# PWM-Power-Box_simplified_R1_0.net
KiCad netlist of a schematic drawn in EAGLE
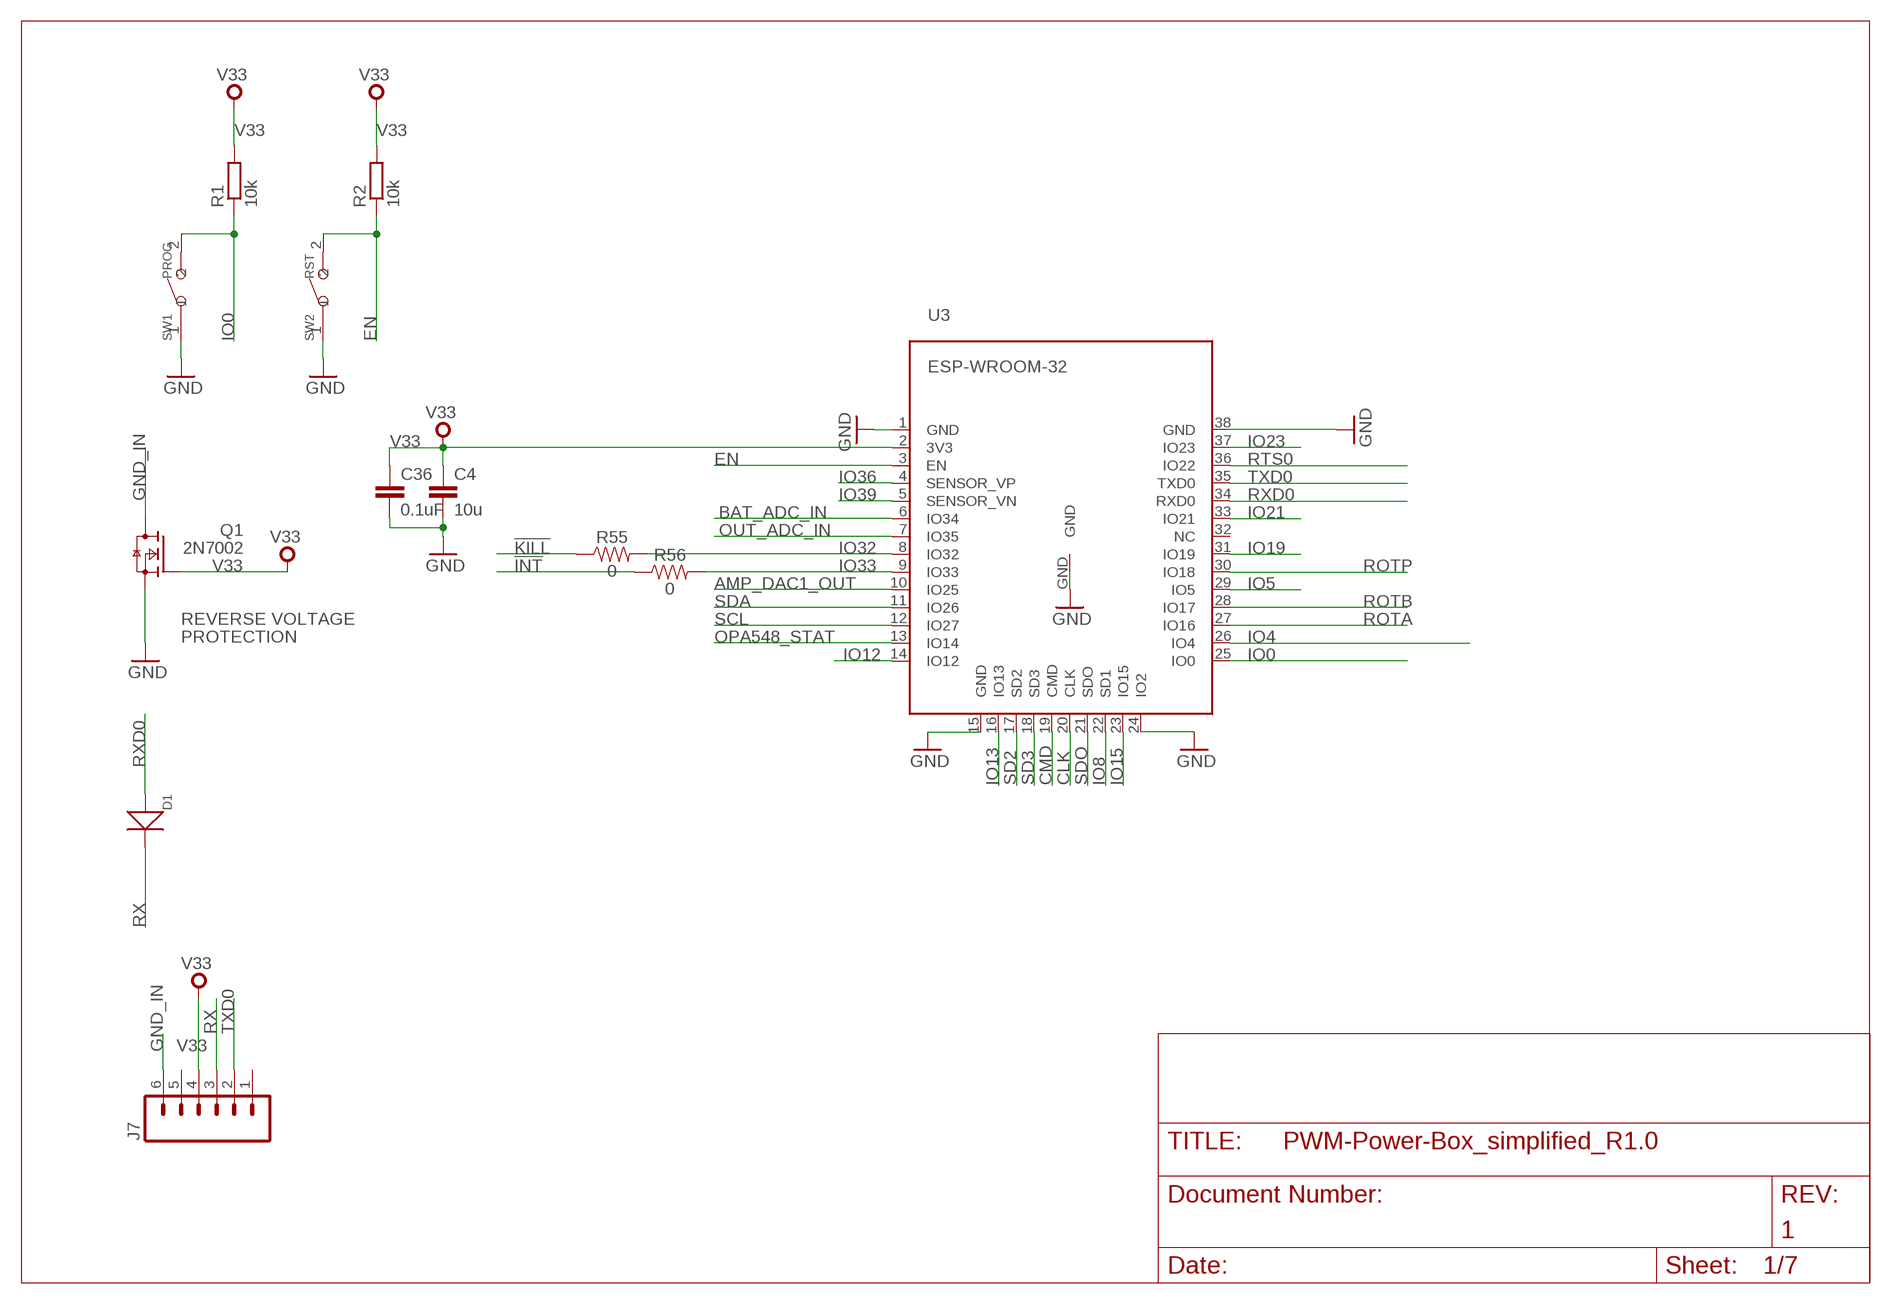
[diagram p0: schematic, sheet 1]
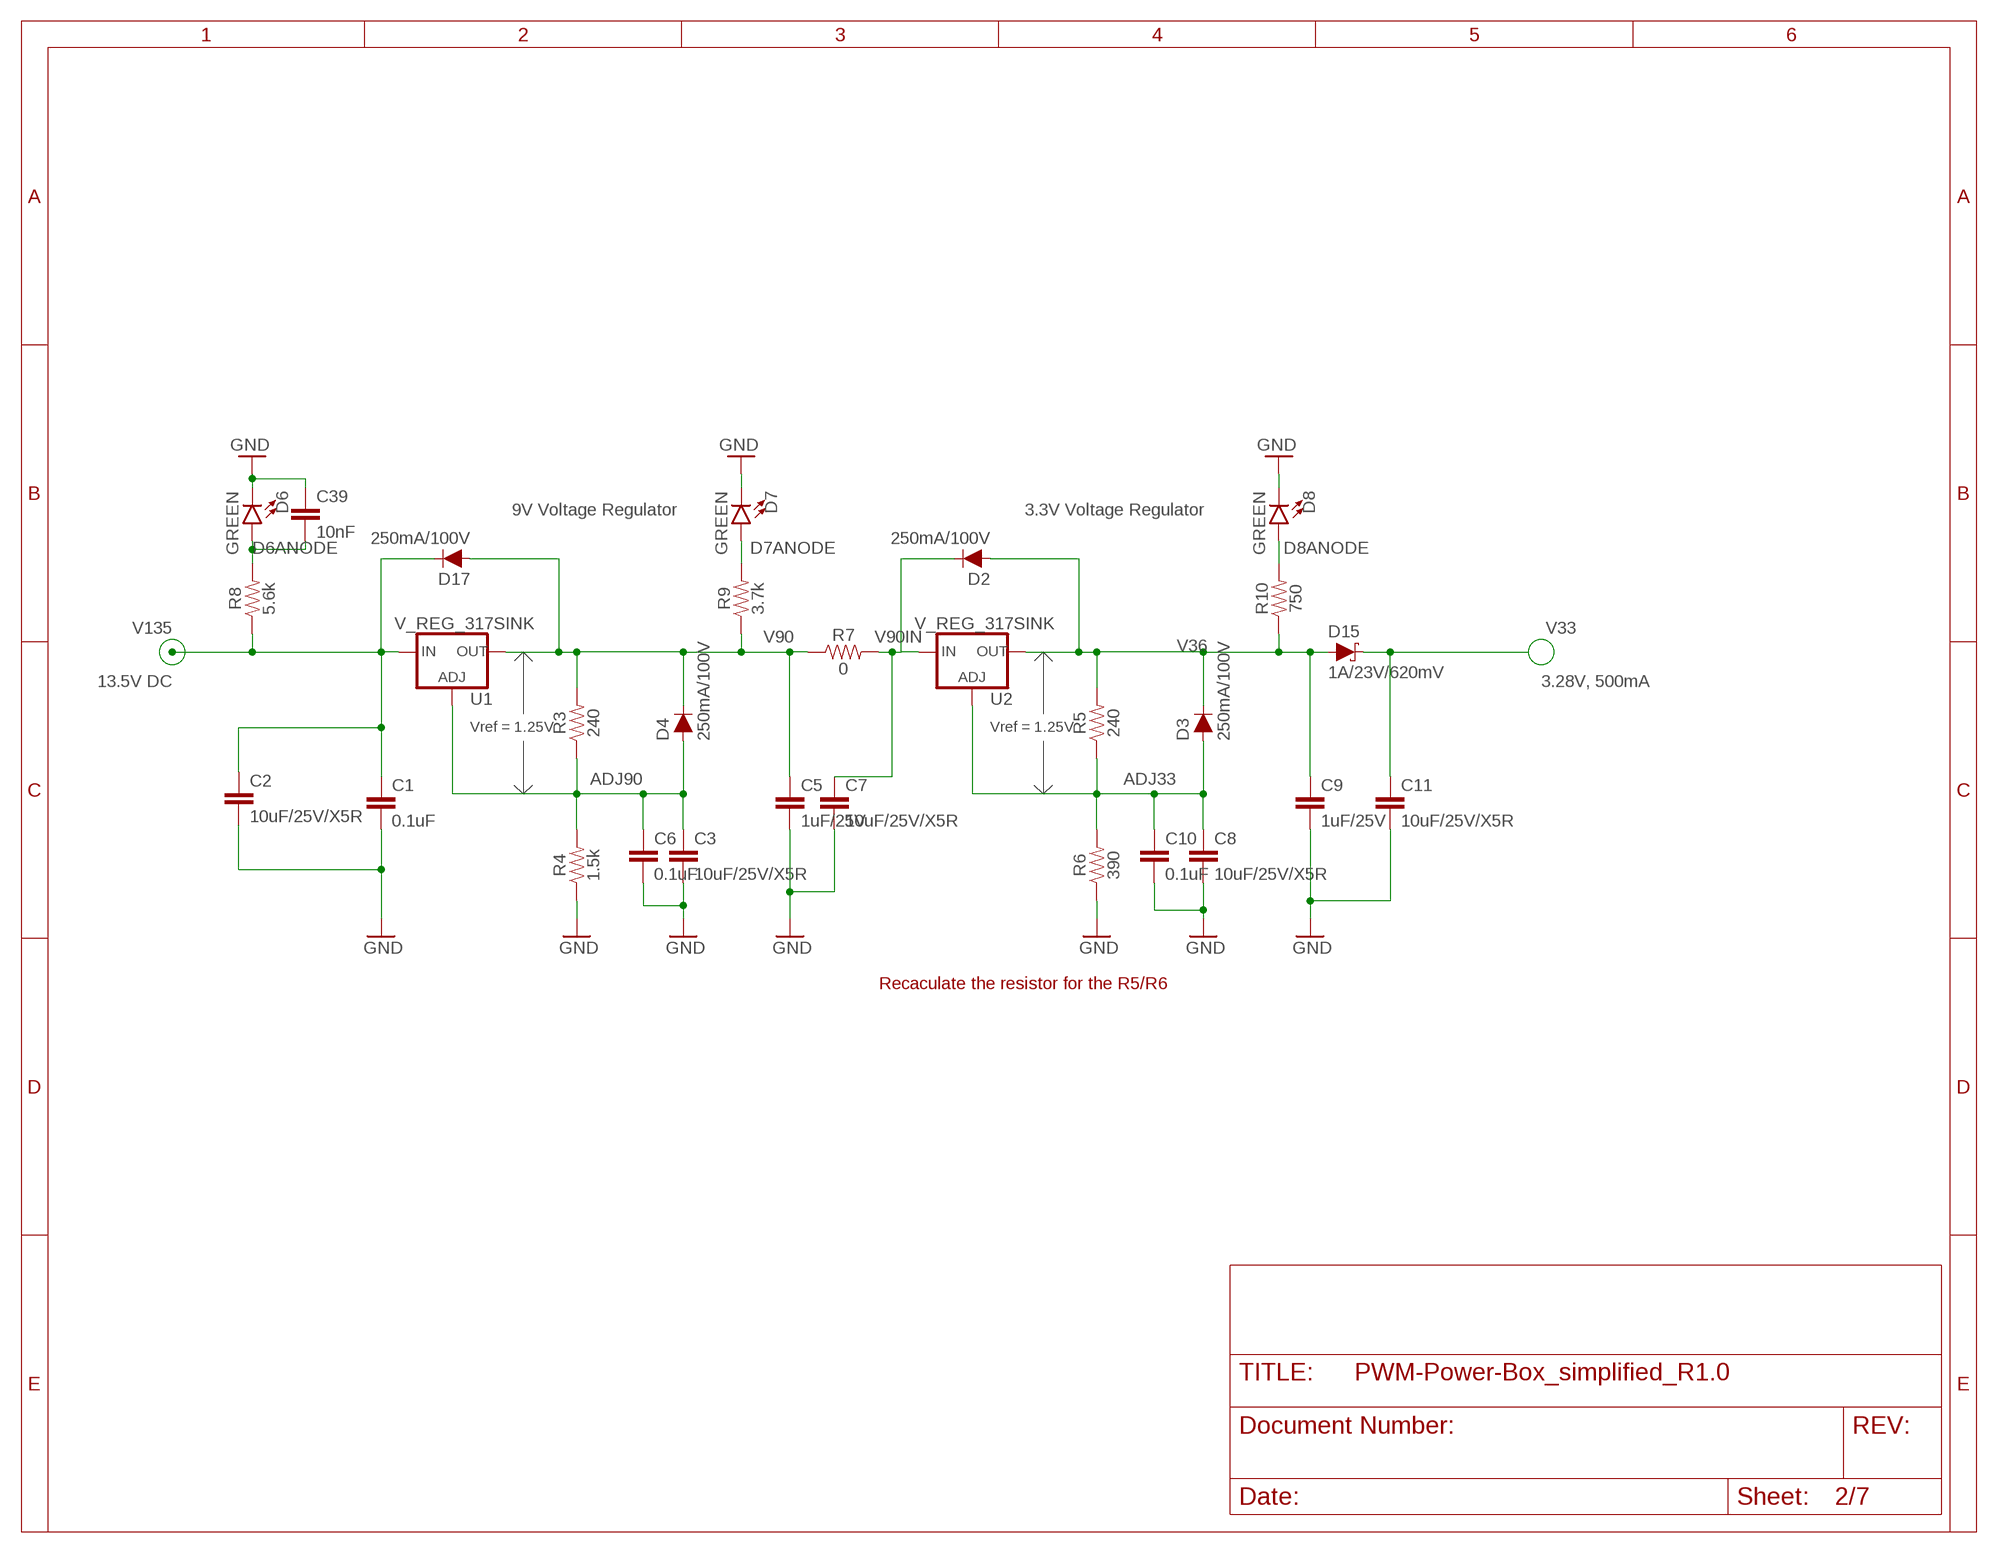
[diagram p1: schematic, sheet 2]
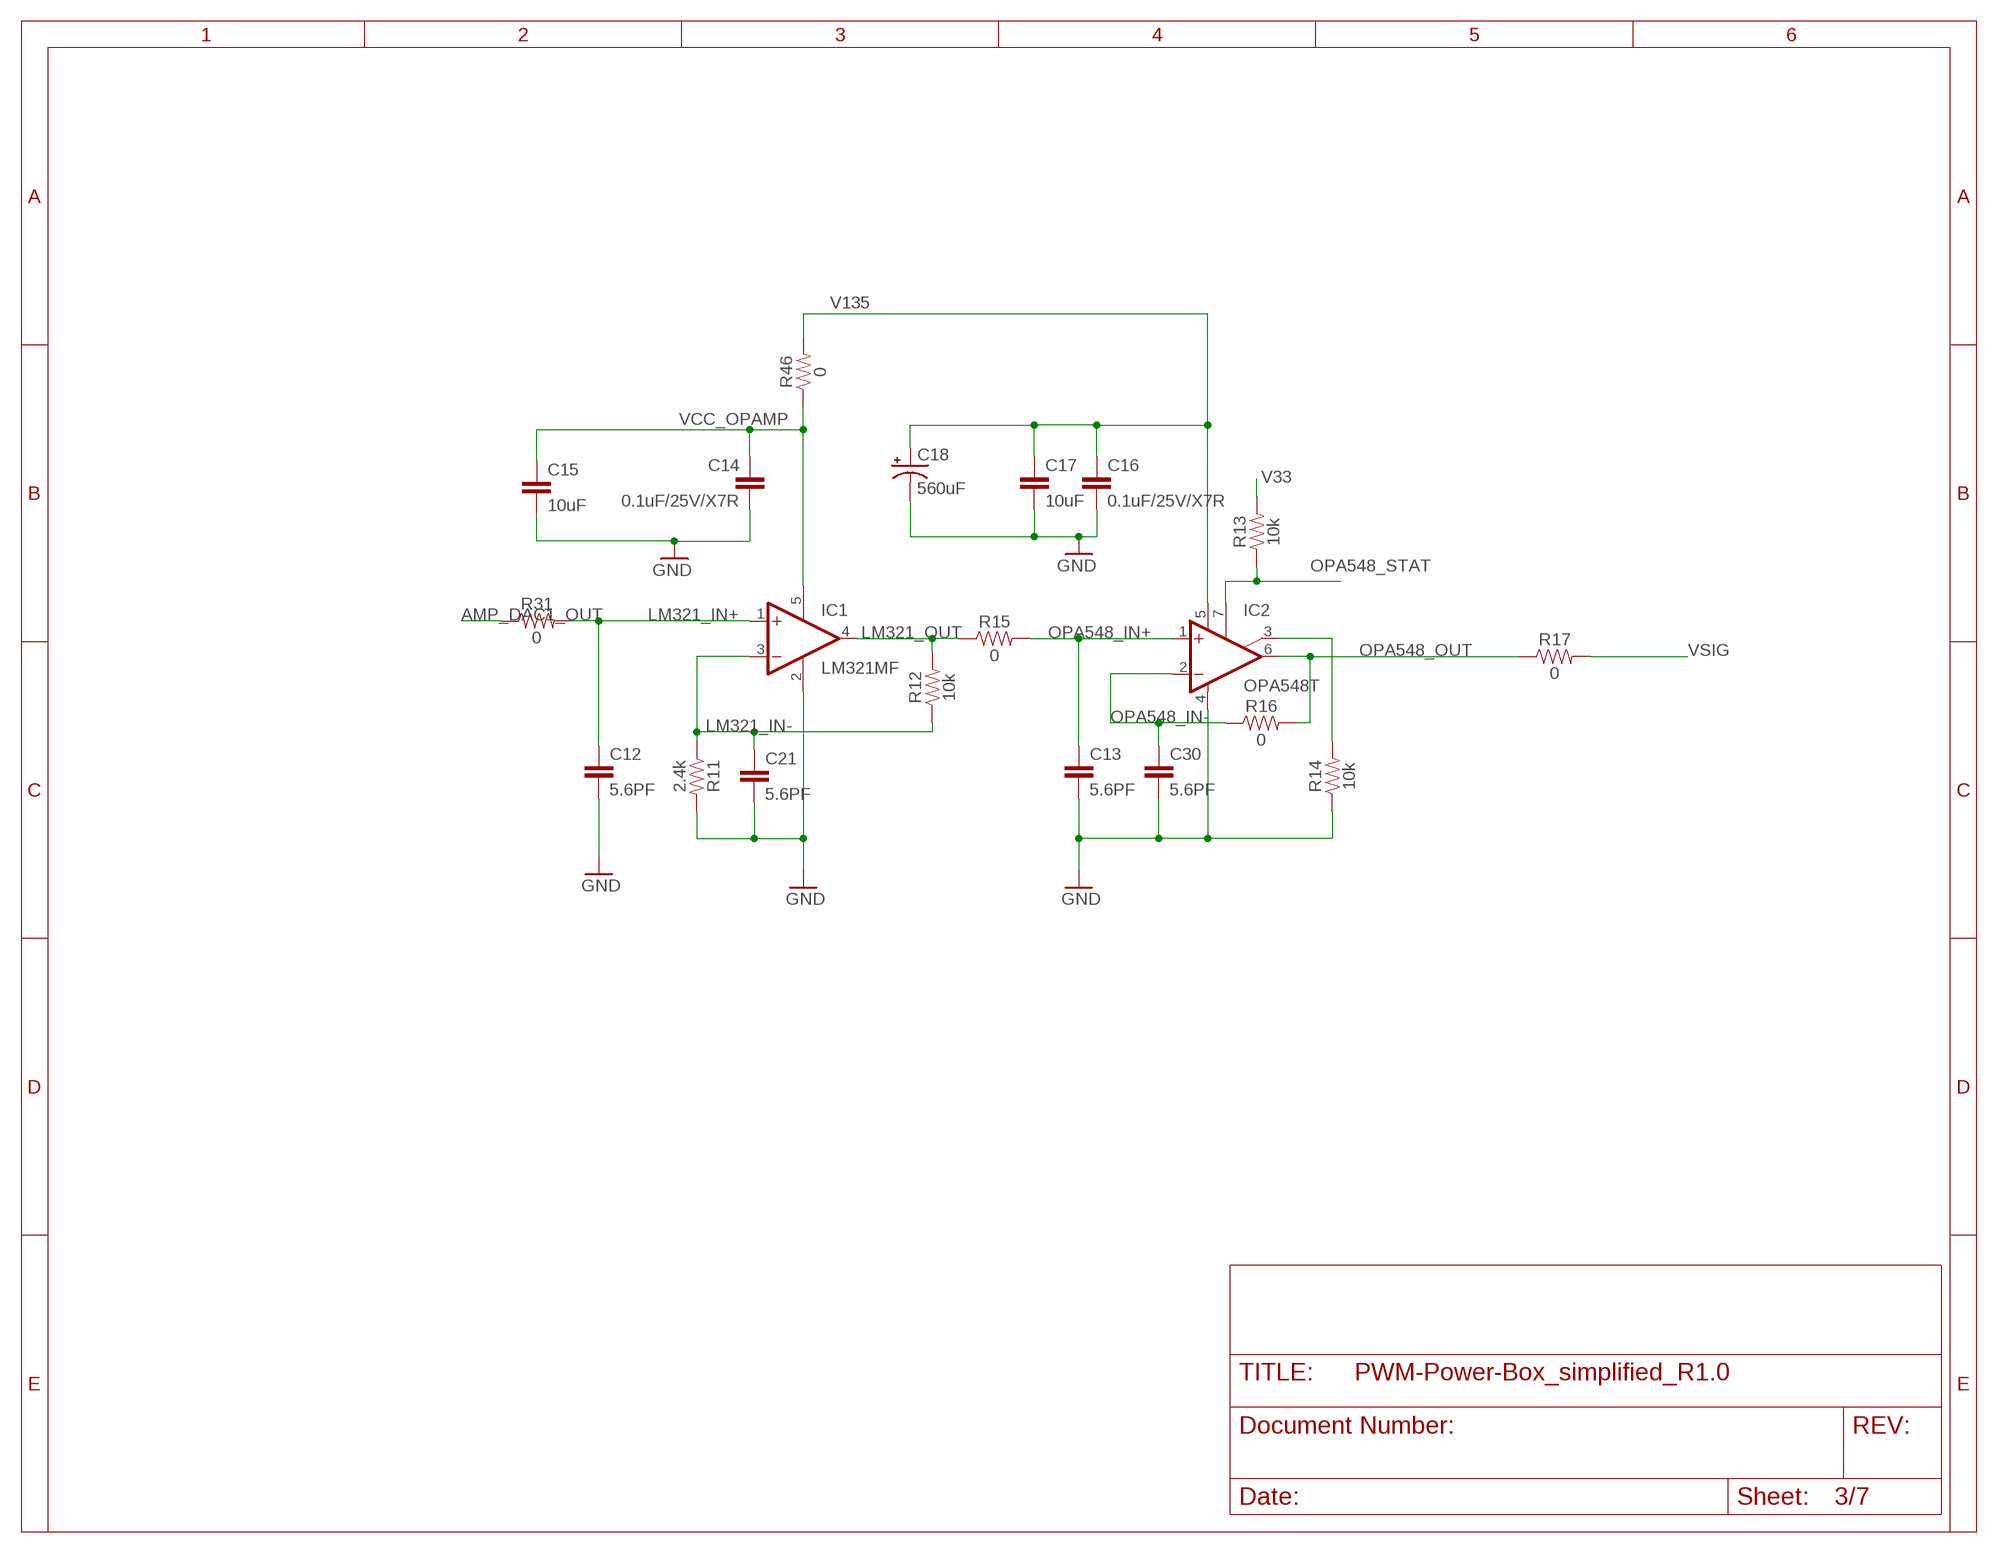
[diagram p2: schematic, sheet 3]
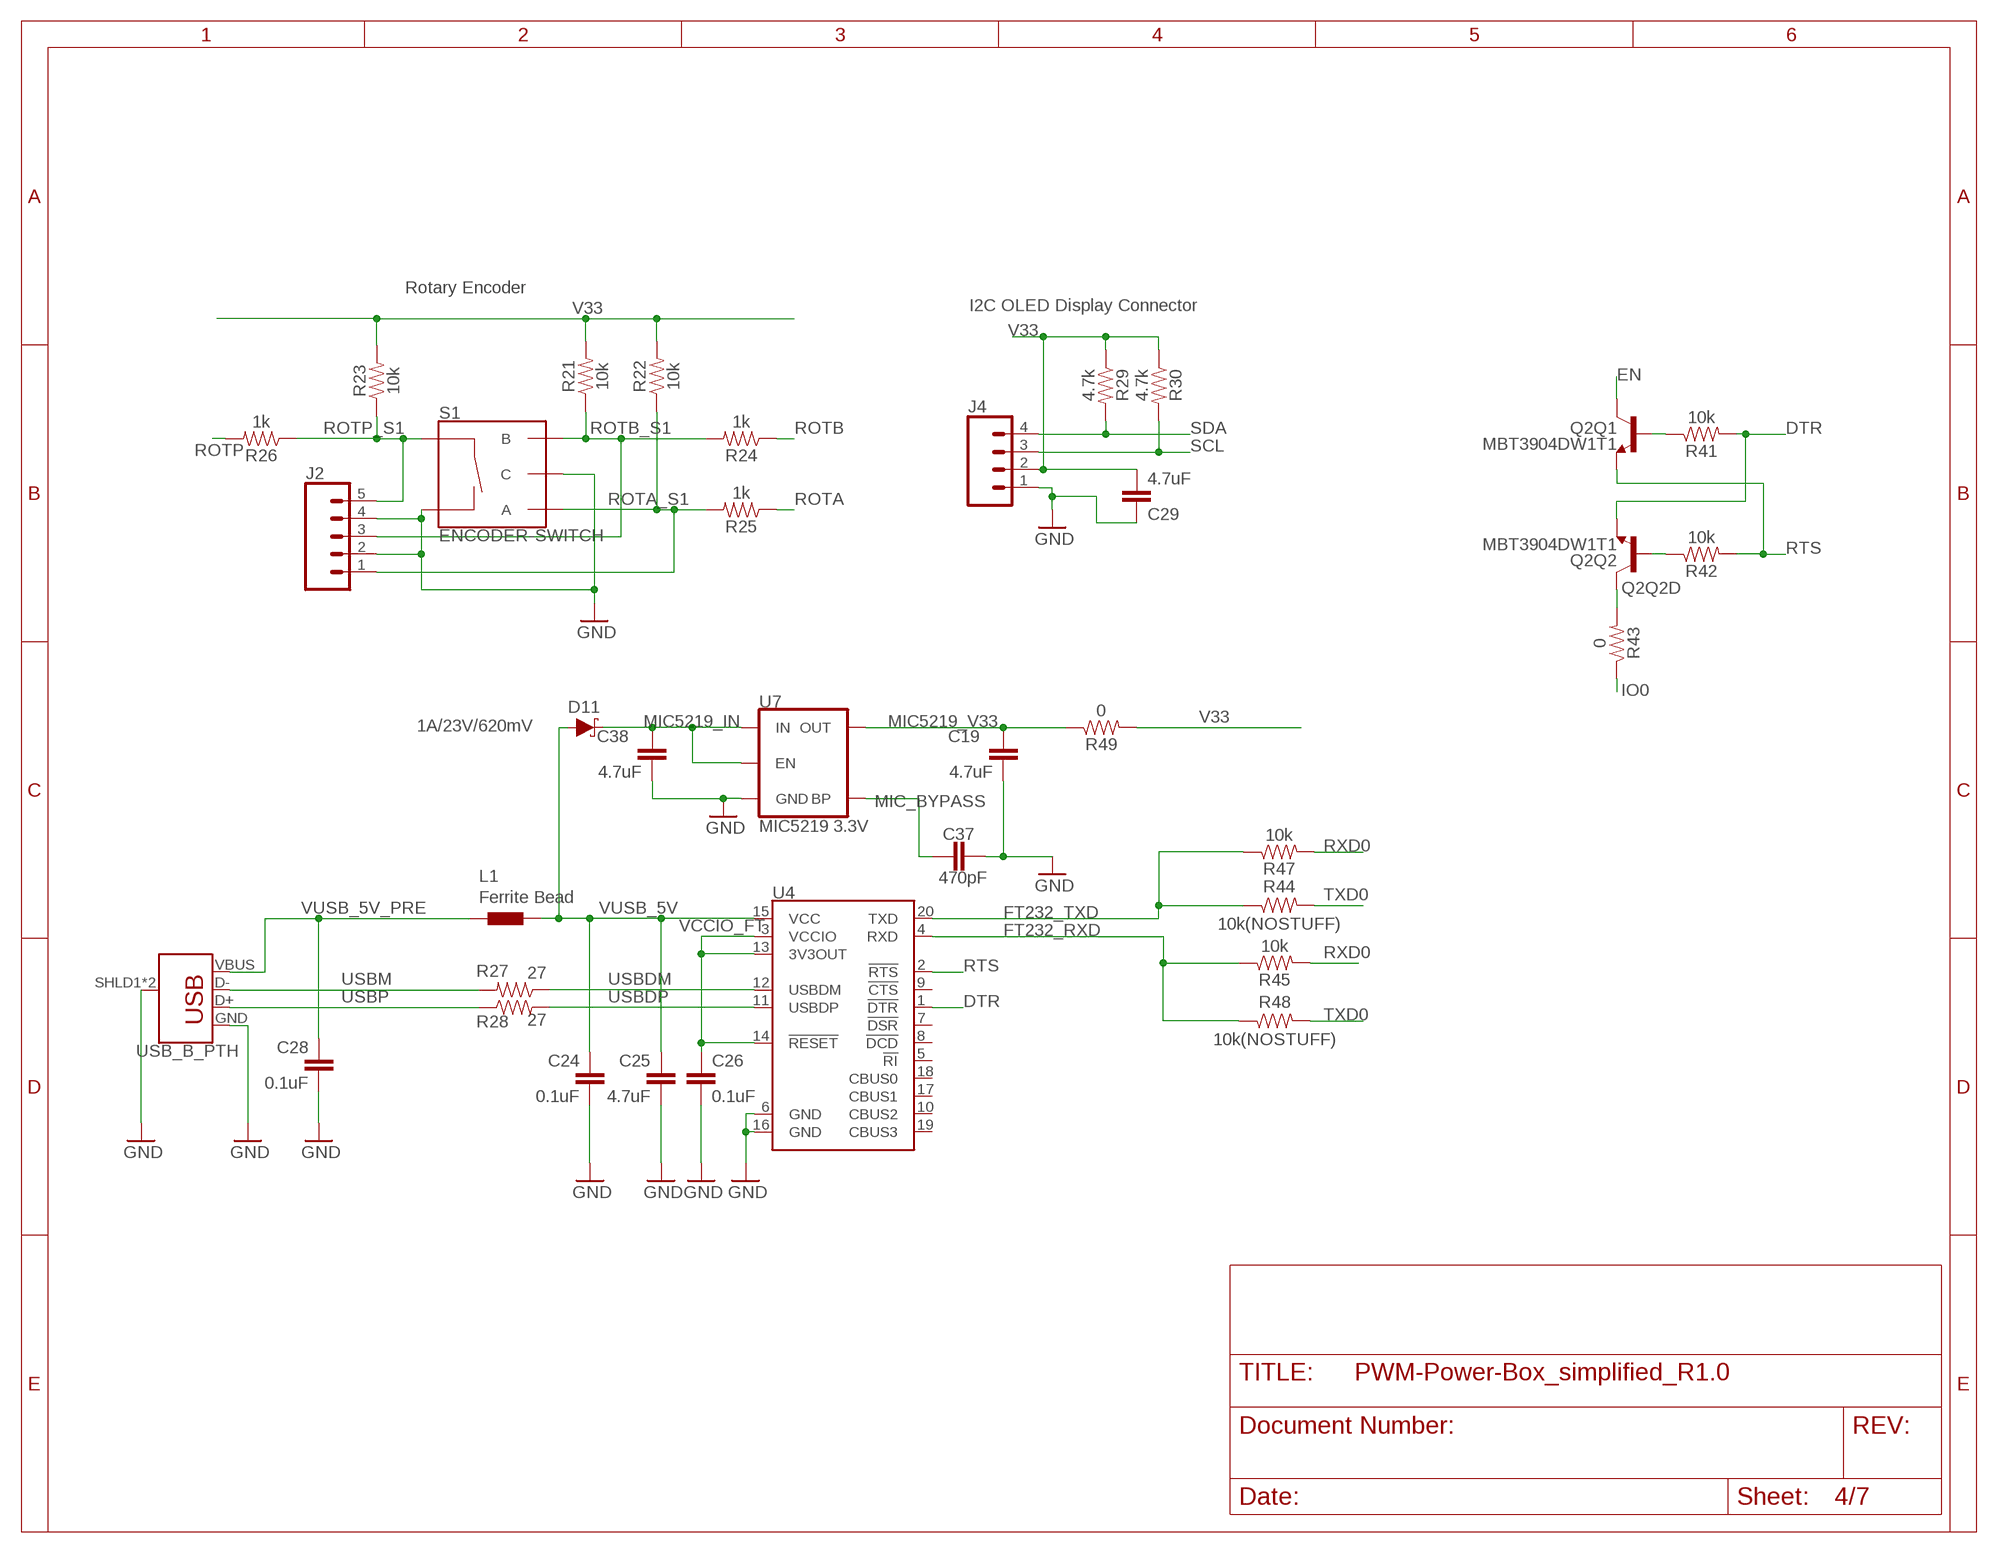
[diagram p3: schematic, sheet 4]
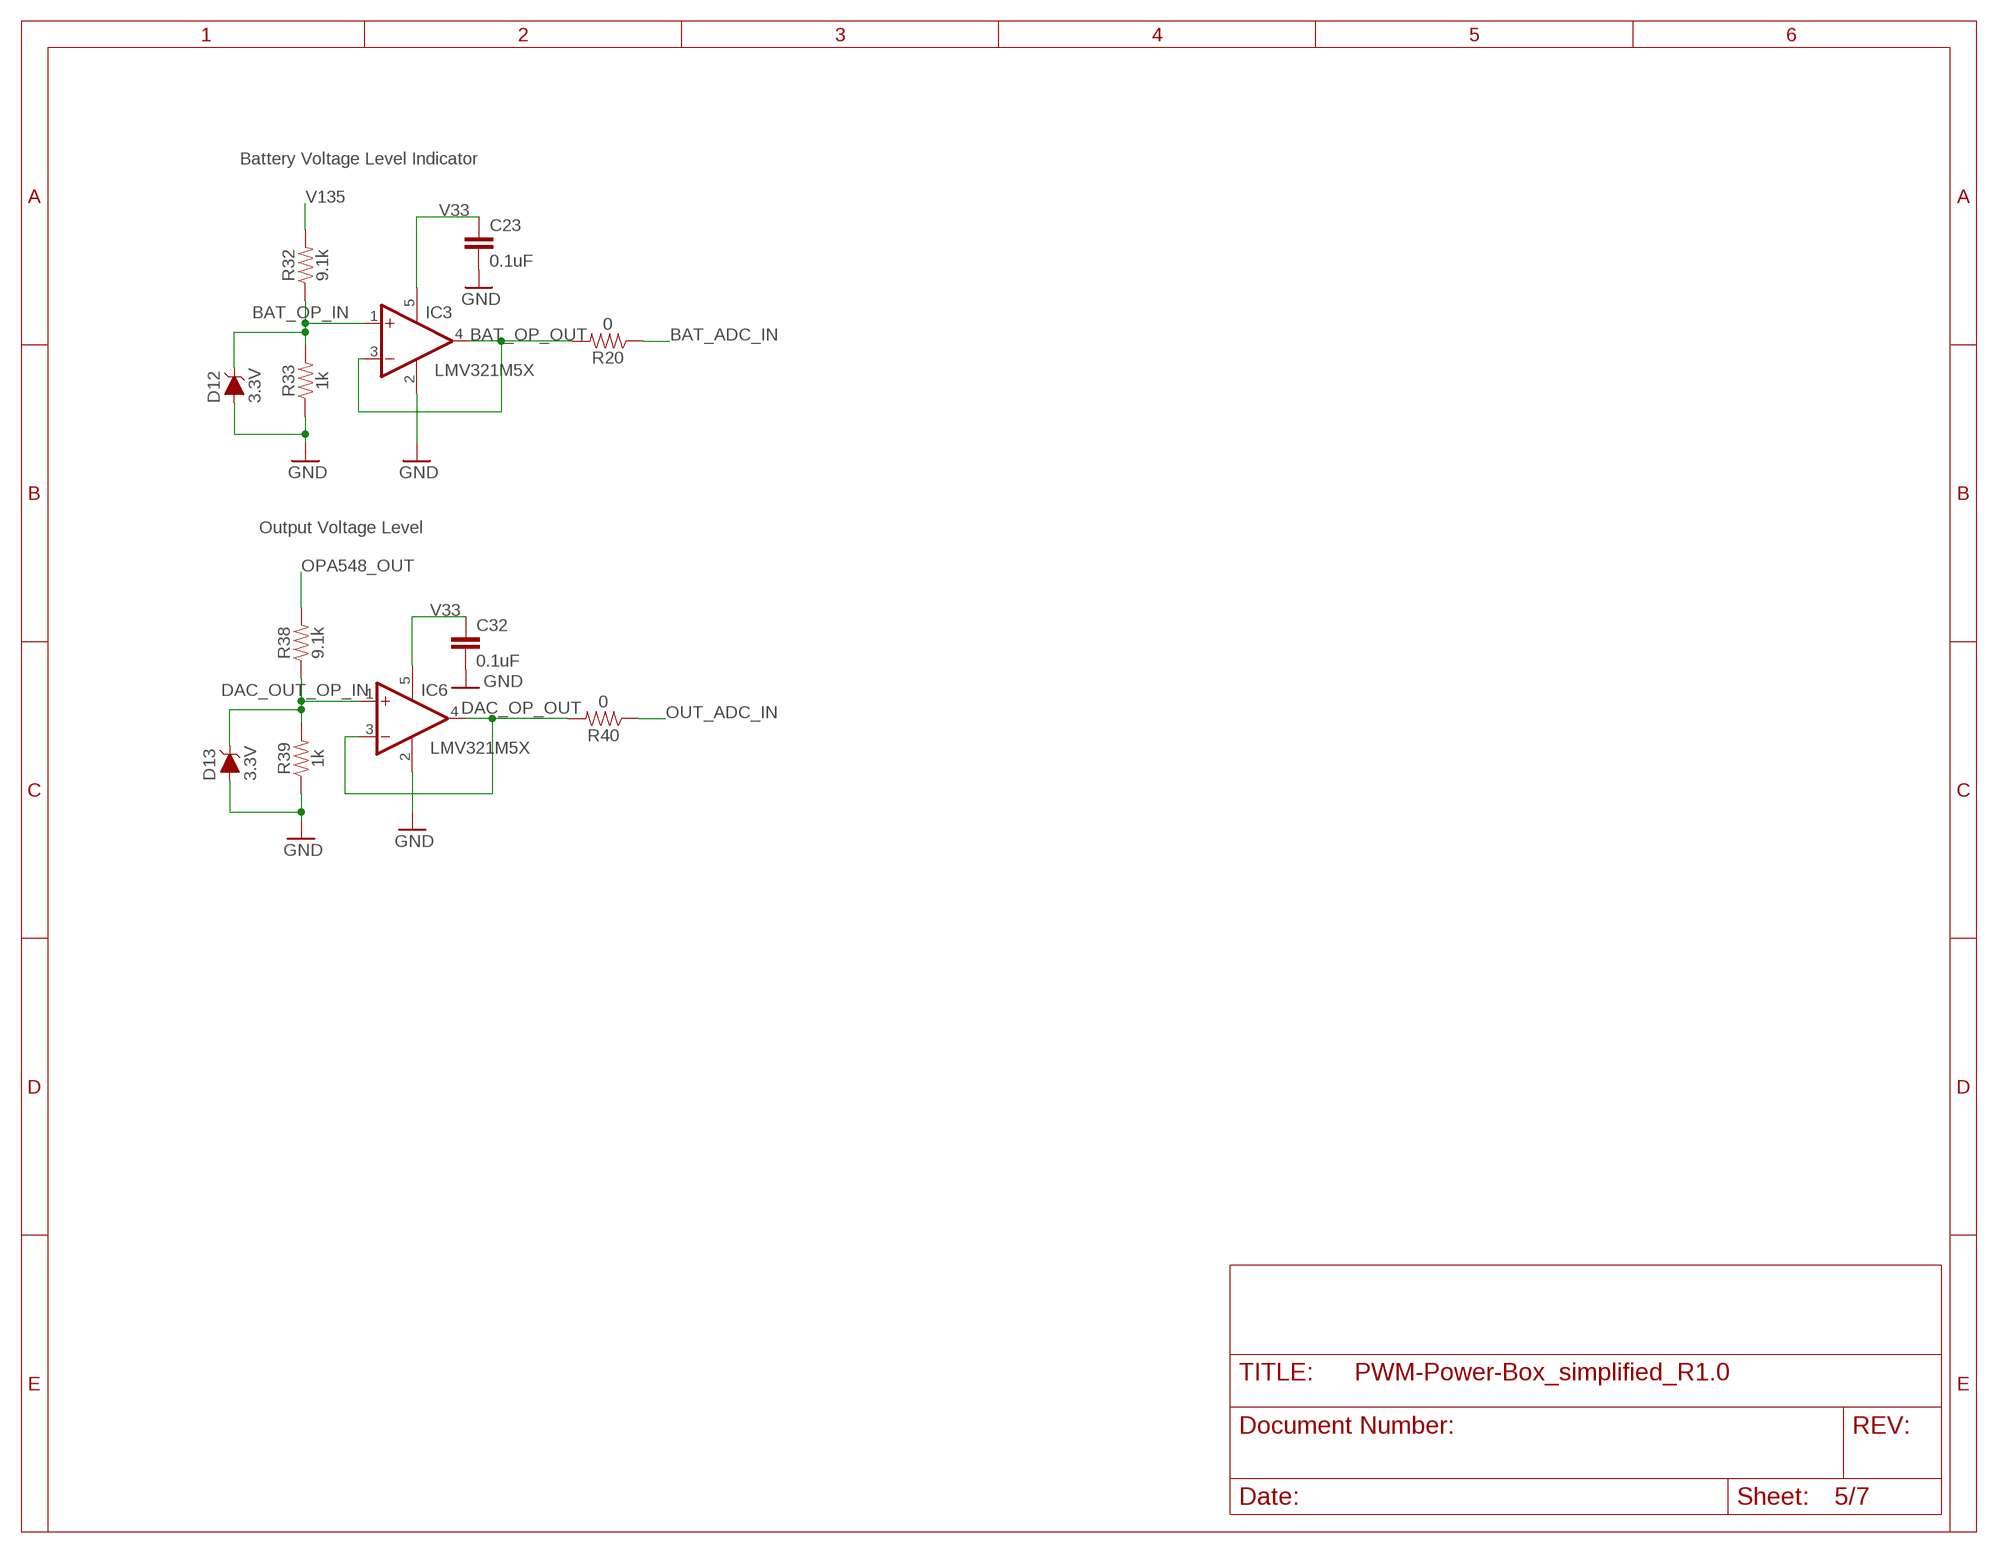
[diagram p4: schematic, sheet 5]
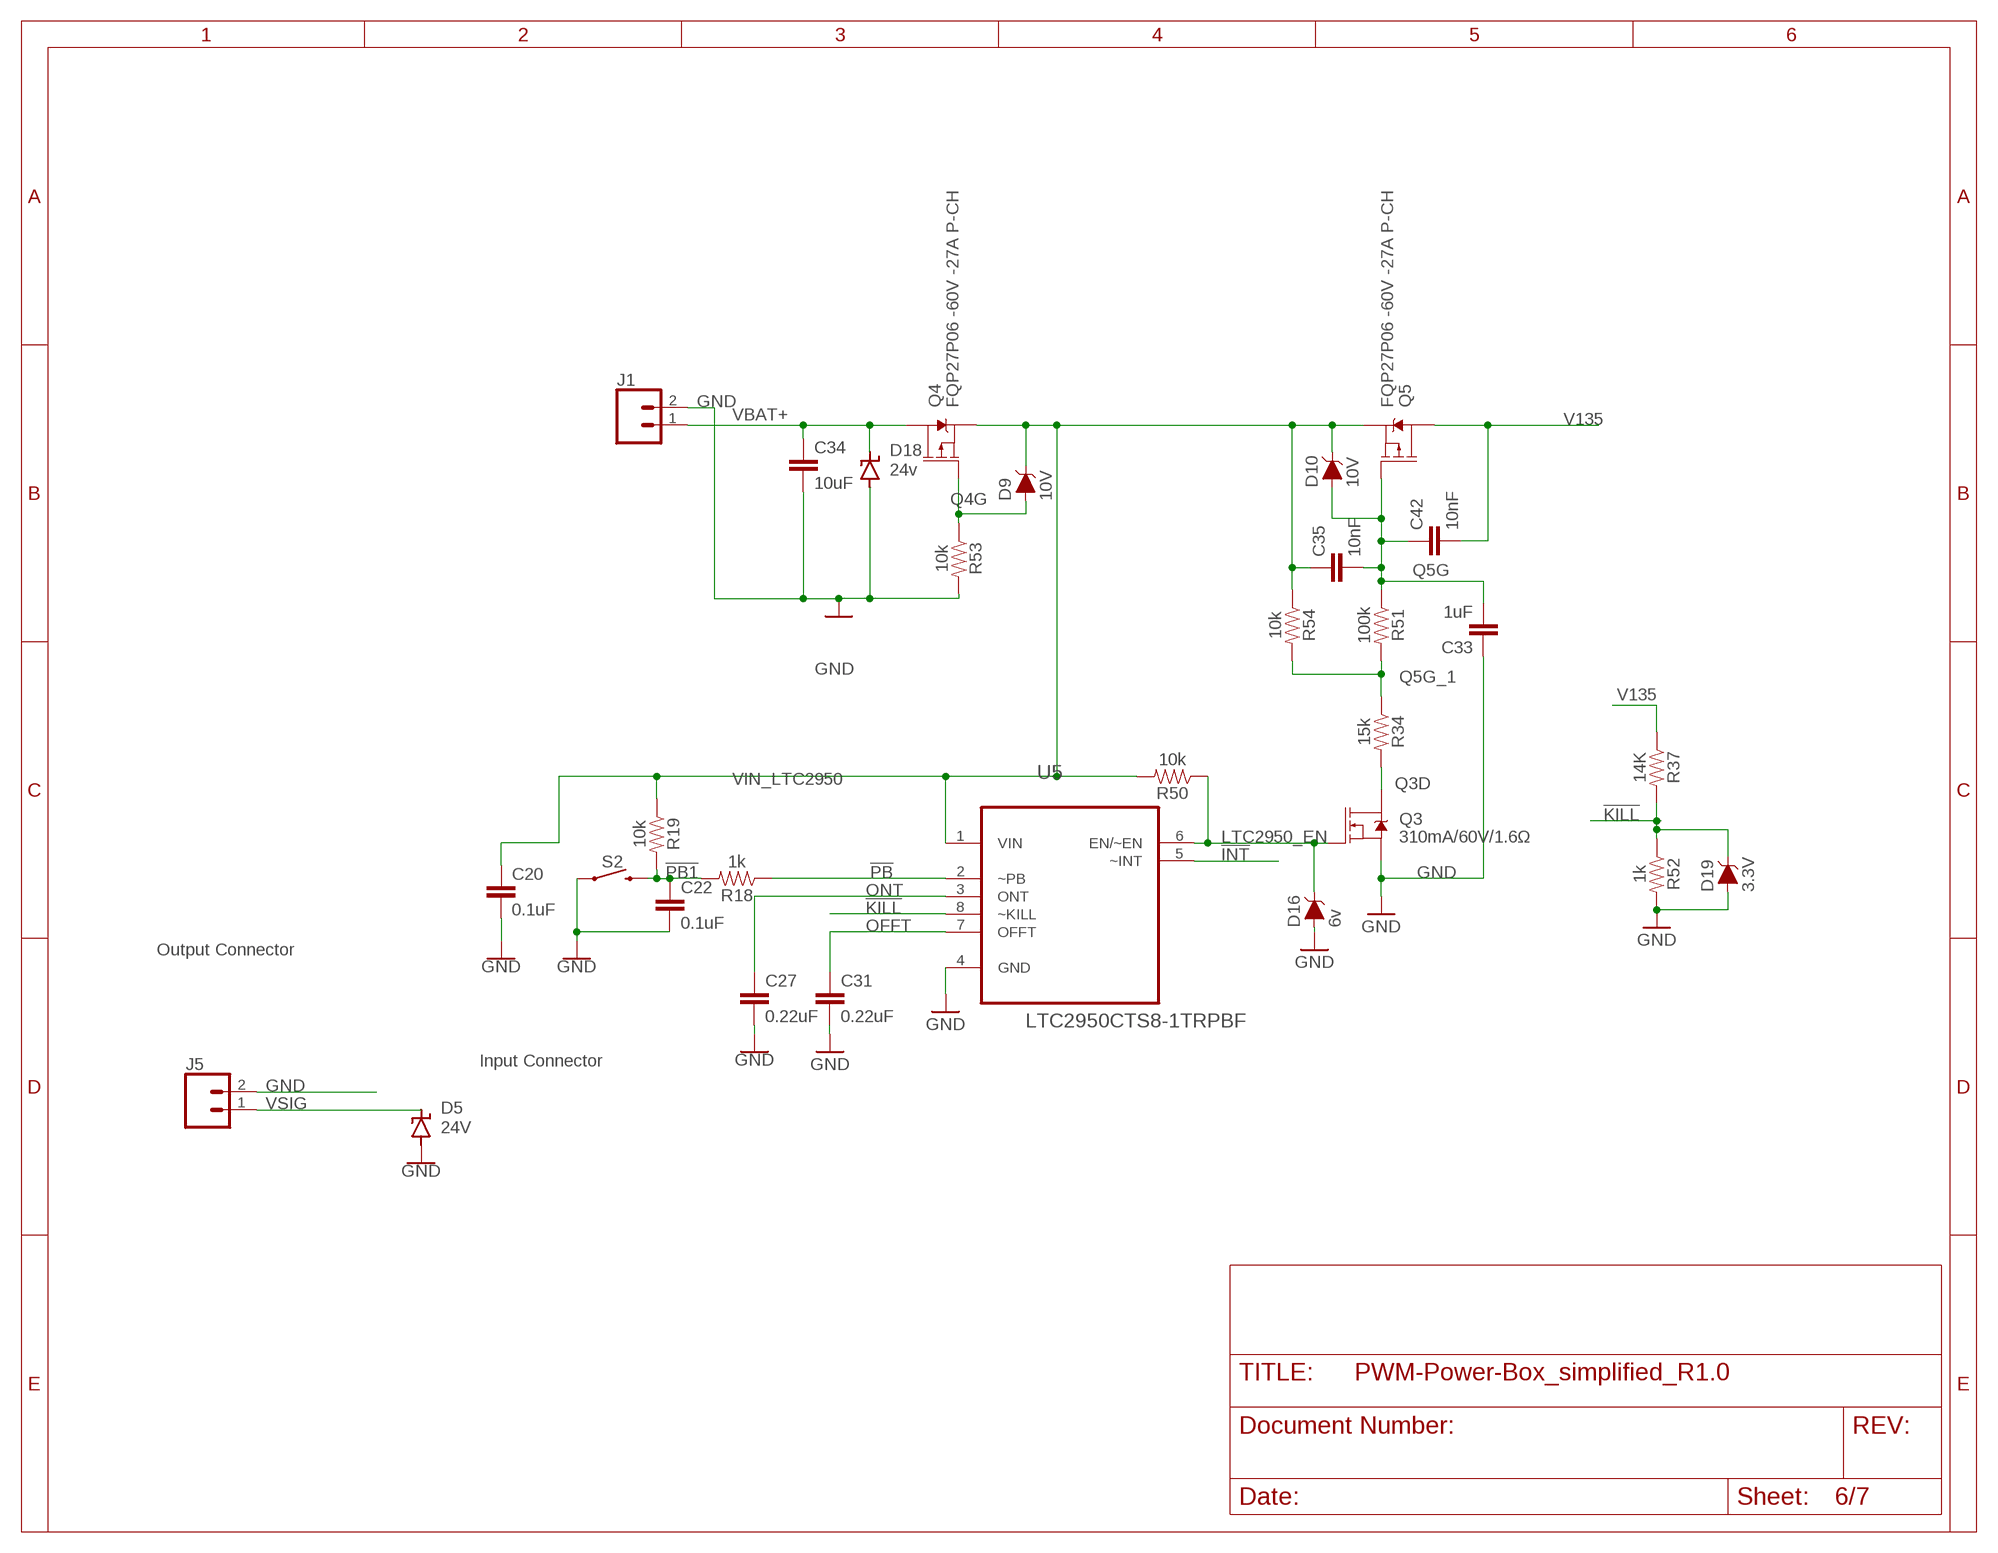
[diagram p5: schematic, sheet 6]

(export (version "E")
  (design (tool "Eeschema 10.0.6"))
  (components
    (comp (ref "C23")
      (value "0.1uF")
      (footprint "eagle-import:0603")
      (libsource (lib "eagle-import") (part "5.6PF-0603-50V-5%"))
    )
    (comp (ref "C32")
      (value "0.1uF")
      (footprint "eagle-import:0603")
      (libsource (lib "eagle-import") (part "5.6PF-0603-50V-5%"))
    )
    (comp (ref "D12")
      (value "3.3V")
      (footprint "eagle-import:SOD-323")
      (libsource (lib "eagle-import") (part "DIODE-ZENER-MM3Z3V3T1G"))
    )
    (comp (ref "D13")
      (value "3.3V")
      (footprint "eagle-import:SOD-323")
      (libsource (lib "eagle-import") (part "DIODE-ZENER-MM3Z3V3T1G"))
    )
    (comp (ref "IC3")
      (value "LMV321M5X")
      (footprint "eagle-import:SOT23-5")
      (libsource (lib "eagle-import") (part "LMV321?M5X"))
    )
    (comp (ref "IC6")
      (value "LMV321M5X")
      (footprint "eagle-import:SOT23-5")
      (libsource (lib "eagle-import") (part "LMV321?M5X"))
    )
    (comp (ref "R20")
      (value "0")
      (footprint "eagle-import:0603")
      (libsource (lib "eagle-import") (part "1.5KOHM-0603-1/10W-1%"))
    )
    (comp (ref "R32")
      (value "9.1k")
      (footprint "eagle-import:0603")
      (libsource (lib "eagle-import") (part "1.5KOHM-0603-1/10W-1%"))
    )
    (comp (ref "R33")
      (value "1k")
      (footprint "eagle-import:0603")
      (libsource (lib "eagle-import") (part "1.5KOHM-0603-1/10W-1%"))
    )
    (comp (ref "R38")
      (value "9.1k")
      (footprint "eagle-import:0603")
      (libsource (lib "eagle-import") (part "1.5KOHM-0603-1/10W-1%"))
    )
    (comp (ref "R39")
      (value "1k")
      (footprint "eagle-import:0603")
      (libsource (lib "eagle-import") (part "1.5KOHM-0603-1/10W-1%"))
    )
    (comp (ref "R40")
      (value "0")
      (footprint "eagle-import:0603")
      (libsource (lib "eagle-import") (part "1.5KOHM-0603-1/10W-1%"))
    )
    (comp (ref "C4")
      (value "10u")
      (footprint "eagle-import:C0603")
      (libsource (lib "eagle-import") (part "C-EUC0603"))
    )
    (comp (ref "C36")
      (value "0.1uF")
      (footprint "eagle-import:C0603")
      (libsource (lib "eagle-import") (part "C-EUC0603"))
    )
    (comp (ref "D1")
      (value "DIODE'0805'")
      (footprint "eagle-import:SOD-323")
      (libsource (lib "eagle-import") (part "DIODE'0805'"))
    )
    (comp (ref "J7")
      (value "M06SILK_FEMALE_PTH")
      (footprint "eagle-import:1X06")
      (libsource (lib "eagle-import") (part "M06SILK_FEMALE_PTH"))
    )
    (comp (ref "Q1")
      (value "2N7002")
      (footprint "eagle-import:SOT23")
      (libsource (lib "eagle-import") (part "2N7002E"))
    )
    (comp (ref "R1")
      (value "10k")
      (footprint "eagle-import:R0603")
      (libsource (lib "eagle-import") (part "R-EU_R0603"))
    )
    (comp (ref "R2")
      (value "10k")
      (footprint "eagle-import:R0603")
      (libsource (lib "eagle-import") (part "R-EU_R0603"))
    )
    (comp (ref "R55")
      (value "0")
      (footprint "eagle-import:0603")
      (libsource (lib "eagle-import") (part "1KOHM-0603-1/10W-1%"))
    )
    (comp (ref "R56")
      (value "0")
      (footprint "eagle-import:0603")
      (libsource (lib "eagle-import") (part "1KOHM-0603-1/10W-1%"))
    )
    (comp (ref "SW1")
      (value "PROG")
      (footprint "eagle-import:SW2-4.0-6.0X3.0X2.5MM")
      (libsource (lib "eagle-import") (part "SMD-BUTTON(2P-6.0X3.0X2.5MM)-DHT-1163S"))
    )
    (comp (ref "SW2")
      (value "RST")
      (footprint "eagle-import:SW2-4.0-6.0X3.0X2.5MM")
      (libsource (lib "eagle-import") (part "SMD-BUTTON(2P-6.0X3.0X2.5MM)-DHT-1163S"))
    )
    (comp (ref "U3")
      (value "ESP-WROOM-32")
      (footprint "eagle-import:ESP-WROOM-32")
      (libsource (lib "eagle-import") (part "ESP-WROOM-32"))
    )
    (comp (ref "C20")
      (value "0.1uF")
      (footprint "eagle-import:0603")
      (libsource (lib "eagle-import") (part "10UF-0603-6.3V-20%"))
    )
    (comp (ref "C22")
      (value "0.1uF")
      (footprint "eagle-import:0603")
      (libsource (lib "eagle-import") (part "10UF-0603-6.3V-20%"))
    )
    (comp (ref "C27")
      (value "0.22uF")
      (footprint "eagle-import:0603")
      (libsource (lib "eagle-import") (part "10UF-0603-6.3V-20%"))
    )
    (comp (ref "C31")
      (value "0.22uF")
      (footprint "eagle-import:0603")
      (libsource (lib "eagle-import") (part "10UF-0603-6.3V-20%"))
    )
    (comp (ref "C33")
      (value "1uF")
      (footprint "eagle-import:0603")
      (libsource (lib "eagle-import") (part "10UF-0603-6.3V-20%"))
    )
    (comp (ref "C34")
      (value "10uF")
      (footprint "eagle-import:1210")
      (libsource (lib "eagle-import") (part "10UF-1210-50V-20%"))
    )
    (comp (ref "C35")
      (value "10nF")
      (footprint "eagle-import:0603")
      (libsource (lib "eagle-import") (part "10UF-0603-6.3V-20%"))
    )
    (comp (ref "C42")
      (value "10nF")
      (footprint "eagle-import:0603")
      (libsource (lib "eagle-import") (part "10UF-0603-6.3V-20%"))
    )
    (comp (ref "D5")
      (value "24V")
      (footprint "eagle-import:SMBG")
      (libsource (lib "eagle-import") (part "SUPPRESSOR-SMBG"))
    )
    (comp (ref "D9")
      (value "10V")
      (footprint "eagle-import:SOD-323")
      (libsource (lib "eagle-import") (part "DIODE-ZENER-BZT52C3V6S"))
    )
    (comp (ref "D10")
      (value "10V")
      (footprint "eagle-import:SOD-323")
      (libsource (lib "eagle-import") (part "DIODE-ZENER-BZT52C3V6S"))
    )
    (comp (ref "D16")
      (value "6v")
      (footprint "eagle-import:SOD-323")
      (libsource (lib "eagle-import") (part "DIODE-ZENER-BZT52C3V6S"))
    )
    (comp (ref "D18")
      (value "24v")
      (footprint "eagle-import:SMBG")
      (libsource (lib "eagle-import") (part "SUPPRESSOR-SMBG"))
    )
    (comp (ref "D19")
      (value "3.3V")
      (footprint "eagle-import:SOD-323")
      (libsource (lib "eagle-import") (part "DIODE-ZENER-BZT52C3V6S"))
    )
    (comp (ref "J1")
      (value "CONN_025MM")
      (footprint "eagle-import:SCREWTERMINAL-5MM-2")
      (libsource (lib "eagle-import") (part "CONN_025MM"))
    )
    (comp (ref "J5")
      (value "CONN_025MM")
      (footprint "eagle-import:SCREWTERMINAL-5MM-2")
      (libsource (lib "eagle-import") (part "CONN_025MM"))
    )
    (comp (ref "Q3")
      (value "310mA/60V/1.6Ω")
      (footprint "eagle-import:SOT323")
      (libsource (lib "eagle-import") (part "MOSFET-NCH-2N7002PW"))
    )
    (comp (ref "Q4")
      (value "FQP27P06 -60V -27A P-CH")
      (footprint "eagle-import:TO220V")
      (libsource (lib "eagle-import") (part "MOSFET_PCH-NDP6020P"))
    )
    (comp (ref "Q5")
      (value "FQP27P06 -60V -27A P-CH")
      (footprint "eagle-import:TO220V")
      (libsource (lib "eagle-import") (part "MOSFET_PCH-NDP6020P"))
    )
    (comp (ref "R18")
      (value "1k")
      (footprint "eagle-import:0603")
      (libsource (lib "eagle-import") (part "100KOHM-0603-1/10W-1%"))
    )
    (comp (ref "R19")
      (value "10k")
      (footprint "eagle-import:0603")
      (libsource (lib "eagle-import") (part "100KOHM-0603-1/10W-1%"))
    )
    (comp (ref "R34")
      (value "15k")
      (footprint "eagle-import:0603")
      (libsource (lib "eagle-import") (part "100KOHM-0603-1/10W-1%"))
    )
    (comp (ref "R37")
      (value "14K")
      (footprint "eagle-import:0603")
      (libsource (lib "eagle-import") (part "100KOHM-0603-1/10W-1%"))
    )
    (comp (ref "R50")
      (value "10k")
      (footprint "eagle-import:0603")
      (libsource (lib "eagle-import") (part "100KOHM-0603-1/10W-1%"))
    )
    (comp (ref "R51")
      (value "100k")
      (footprint "eagle-import:0603")
      (libsource (lib "eagle-import") (part "100KOHM-0603-1/10W-1%"))
    )
    (comp (ref "R52")
      (value "1k")
      (footprint "eagle-import:0603")
      (libsource (lib "eagle-import") (part "100KOHM-0603-1/10W-1%"))
    )
    (comp (ref "R53")
      (value "10k")
      (footprint "eagle-import:0603")
      (libsource (lib "eagle-import") (part "100KOHM-0603-1/10W-1%"))
    )
    (comp (ref "R54")
      (value "10k")
      (footprint "eagle-import:0603")
      (libsource (lib "eagle-import") (part "100KOHM-0603-1/10W-1%"))
    )
    (comp (ref "S2")
      (value "MOMENTARY-SWITCH-SPST-PTH-RIGHT-ANGLE-KIT")
      (footprint "eagle-import:TACTILE_SWITCH_PTH_RIGHT_ANGLE_KIT")
      (libsource (lib "eagle-import") (part "MOMENTARY-SWITCH-SPST-PTH-RIGHT-ANGLE-KIT"))
    )
    (comp (ref "U5")
      (value "LTC2950CTS8-1TRPBF")
      (footprint "eagle-import:SOT65P280X100-8N")
      (fields (field (name "MF") "Linear Technology/Analog") (field (name "MP") "LTC2950CTS8-1#TRPBF"))
      (libsource (lib "eagle-import") (part "LTC2950CTS8-1TRPBF"))
    )
    (comp (ref "C19")
      (value "4.7uF")
      (footprint "eagle-import:0603")
      (libsource (lib "eagle-import") (part "5.6PF-0603-50V-5%"))
    )
    (comp (ref "C24")
      (value "0.1uF")
      (footprint "eagle-import:0603")
      (libsource (lib "eagle-import") (part "5.6PF-0603-50V-5%"))
    )
    (comp (ref "C25")
      (value "4.7uF")
      (footprint "eagle-import:0603")
      (libsource (lib "eagle-import") (part "5.6PF-0603-50V-5%"))
    )
    (comp (ref "C26")
      (value "0.1uF")
      (footprint "eagle-import:0603")
      (libsource (lib "eagle-import") (part "5.6PF-0603-50V-5%"))
    )
    (comp (ref "C28")
      (value "0.1uF")
      (footprint "eagle-import:0603")
      (libsource (lib "eagle-import") (part "5.6PF-0603-50V-5%"))
    )
    (comp (ref "C29")
      (value "4.7uF")
      (footprint "eagle-import:0603")
      (libsource (lib "eagle-import") (part "5.6PF-0603-50V-5%"))
    )
    (comp (ref "C37")
      (value "470pF")
      (footprint "eagle-import:0603")
      (libsource (lib "eagle-import") (part "5.6PF-0603-50V-5%"))
    )
    (comp (ref "C38")
      (value "4.7uF")
      (footprint "eagle-import:0603")
      (libsource (lib "eagle-import") (part "5.6PF-0603-50V-5%"))
    )
    (comp (ref "D11")
      (value "1A/23V/620mV")
      (footprint "eagle-import:SOD-323")
      (libsource (lib "eagle-import") (part "DIODE-SCHOTTKY-BAT20J"))
    )
    (comp (ref "J2")
      (value "CONN_05")
      (footprint "eagle-import:1X05")
      (libsource (lib "eagle-import") (part "CONN_05"))
    )
    (comp (ref "J3")
      (value "USB_B_PTH")
      (footprint "eagle-import:USB-B-PTH")
      (libsource (lib "eagle-import") (part "USB_B_PTH"))
    )
    (comp (ref "J4")
      (value "CONN_04")
      (footprint "eagle-import:1X04")
      (libsource (lib "eagle-import") (part "CONN_04"))
    )
    (comp (ref "L1")
      (value "Ferrite Bead")
      (footprint "eagle-import:0402")
      (libsource (lib "eagle-import") (part "BLM15HB121SN1"))
    )
    (comp (ref "Q2")
      (value "MBT3904DW1T1")
      (footprint "eagle-import:SC70-6")
      (libsource (lib "eagle-import") (part "TRANS_NPN_DUAL-MBT3904DW1T1"))
    )
    (comp (ref "R21")
      (value "10k")
      (footprint "eagle-import:0603")
      (libsource (lib "eagle-import") (part "1.5KOHM-0603-1/10W-1%"))
    )
    (comp (ref "R22")
      (value "10k")
      (footprint "eagle-import:0603")
      (libsource (lib "eagle-import") (part "1.5KOHM-0603-1/10W-1%"))
    )
    (comp (ref "R23")
      (value "10k")
      (footprint "eagle-import:0603")
      (libsource (lib "eagle-import") (part "1.5KOHM-0603-1/10W-1%"))
    )
    (comp (ref "R24")
      (value "1k")
      (footprint "eagle-import:0603")
      (libsource (lib "eagle-import") (part "1.5KOHM-0603-1/10W-1%"))
    )
    (comp (ref "R25")
      (value "1k")
      (footprint "eagle-import:0603")
      (libsource (lib "eagle-import") (part "1.5KOHM-0603-1/10W-1%"))
    )
    (comp (ref "R26")
      (value "1k")
      (footprint "eagle-import:0603")
      (libsource (lib "eagle-import") (part "1.5KOHM-0603-1/10W-1%"))
    )
    (comp (ref "R27")
      (value "27")
      (footprint "eagle-import:0603")
      (libsource (lib "eagle-import") (part "1.5KOHM-0603-1/10W-1%"))
    )
    (comp (ref "R28")
      (value "27")
      (footprint "eagle-import:0603")
      (libsource (lib "eagle-import") (part "1.5KOHM-0603-1/10W-1%"))
    )
    (comp (ref "R29")
      (value "4.7k")
      (footprint "eagle-import:0603")
      (libsource (lib "eagle-import") (part "1.5KOHM-0603-1/10W-1%"))
    )
    (comp (ref "R30")
      (value "4.7k")
      (footprint "eagle-import:0603")
      (libsource (lib "eagle-import") (part "1.5KOHM-0603-1/10W-1%"))
    )
    (comp (ref "R41")
      (value "10k")
      (footprint "eagle-import:0603")
      (libsource (lib "eagle-import") (part "1.5KOHM-0603-1/10W-1%"))
    )
    (comp (ref "R42")
      (value "10k")
      (footprint "eagle-import:0603")
      (libsource (lib "eagle-import") (part "1.5KOHM-0603-1/10W-1%"))
    )
    (comp (ref "R43")
      (value "0")
      (footprint "eagle-import:0603")
      (libsource (lib "eagle-import") (part "1.5KOHM-0603-1/10W-1%"))
    )
    (comp (ref "R44")
      (value "10k(NOSTUFF)")
      (footprint "eagle-import:0603")
      (libsource (lib "eagle-import") (part "1.5KOHM-0603-1/10W-1%"))
    )
    (comp (ref "R45")
      (value "10k")
      (footprint "eagle-import:0603")
      (libsource (lib "eagle-import") (part "1.5KOHM-0603-1/10W-1%"))
    )
    (comp (ref "R47")
      (value "10k")
      (footprint "eagle-import:0603")
      (libsource (lib "eagle-import") (part "1.5KOHM-0603-1/10W-1%"))
    )
    (comp (ref "R48")
      (value "10k(NOSTUFF)")
      (footprint "eagle-import:0603")
      (libsource (lib "eagle-import") (part "1.5KOHM-0603-1/10W-1%"))
    )
    (comp (ref "R49")
      (value "0")
      (footprint "eagle-import:0603")
      (libsource (lib "eagle-import") (part "1.5KOHM-0603-1/10W-1%"))
    )
    (comp (ref "S1")
      (value "ENCODER-SWITCH")
      (footprint "eagle-import:ROTARY_ENC_PLAIN")
      (libsource (lib "eagle-import") (part "ENCODER-SWITCH"))
    )
    (comp (ref "U4")
      (value "FT231XS")
      (footprint "eagle-import:SSOP20_L")
      (libsource (lib "eagle-import") (part "FT231XS"))
    )
    (comp (ref "U7")
      (value "MIC5219 3.3V")
      (footprint "eagle-import:SOT23-5")
      (libsource (lib "eagle-import") (part "V_REG_MIC52193.3V"))
    )
    (comp (ref "C12")
      (value "5.6PF")
      (footprint "eagle-import:0603")
      (libsource (lib "eagle-import") (part "5.6PF-0603-50V-5%"))
    )
    (comp (ref "C13")
      (value "5.6PF")
      (footprint "eagle-import:0603")
      (libsource (lib "eagle-import") (part "5.6PF-0603-50V-5%"))
    )
    (comp (ref "C14")
      (value "0.1uF/25V/X7R")
      (footprint "eagle-import:0603")
      (libsource (lib "eagle-import") (part "5.6PF-0603-50V-5%"))
    )
    (comp (ref "C15")
      (value "10uF")
      (footprint "eagle-import:1206")
      (libsource (lib "eagle-import") (part "10UF-1206-6.3V-20%"))
    )
    (comp (ref "C16")
      (value "0.1uF/25V/X7R")
      (footprint "eagle-import:0603")
      (libsource (lib "eagle-import") (part "5.6PF-0603-50V-5%"))
    )
    (comp (ref "C17")
      (value "10uF")
      (footprint "eagle-import:1206")
      (libsource (lib "eagle-import") (part "10UF-1206-6.3V-20%"))
    )
    (comp (ref "C18")
      (value "560uF")
      (footprint "eagle-import:PANASONIC_G")
      (libsource (lib "eagle-import") (part "560UF-PANASONIC_G-25V-20%"))
    )
    (comp (ref "C21")
      (value "5.6PF")
      (footprint "eagle-import:0603")
      (libsource (lib "eagle-import") (part "5.6PF-0603-50V-5%"))
    )
    (comp (ref "C30")
      (value "5.6PF")
      (footprint "eagle-import:0603")
      (libsource (lib "eagle-import") (part "5.6PF-0603-50V-5%"))
    )
    (comp (ref "IC1")
      (value "LM321MF")
      (footprint "eagle-import:SOT23-5")
      (libsource (lib "eagle-import") (part "LM321?MF"))
    )
    (comp (ref "IC2")
      (value "OPA548T")
      (footprint "eagle-import:TO220-7")
      (fields (field (name "MF") "TEXAS INSTRUMENTS"))
      (libsource (lib "eagle-import") (part "OPA548T"))
    )
    (comp (ref "R11")
      (value "2.4k")
      (footprint "eagle-import:0603")
      (libsource (lib "eagle-import") (part "1.5KOHM-0603-1/10W-1%"))
    )
    (comp (ref "R12")
      (value "10k")
      (footprint "eagle-import:0603")
      (libsource (lib "eagle-import") (part "1.5KOHM-0603-1/10W-1%"))
    )
    (comp (ref "R13")
      (value "10k")
      (footprint "eagle-import:0603")
      (libsource (lib "eagle-import") (part "1.5KOHM-0603-1/10W-1%"))
    )
    (comp (ref "R14")
      (value "10k")
      (footprint "eagle-import:0603")
      (libsource (lib "eagle-import") (part "1.5KOHM-0603-1/10W-1%"))
    )
    (comp (ref "R15")
      (value "0")
      (footprint "eagle-import:0603")
      (libsource (lib "eagle-import") (part "1.5KOHM-0603-1/10W-1%"))
    )
    (comp (ref "R16")
      (value "0")
      (footprint "eagle-import:0603")
      (libsource (lib "eagle-import") (part "1.5KOHM-0603-1/10W-1%"))
    )
    (comp (ref "R17")
      (value "0")
      (footprint "eagle-import:1210")
      (libsource (lib "eagle-import") (part "0.1OHM-1210-1/2W-1%"))
    )
    (comp (ref "R31")
      (value "0")
      (footprint "eagle-import:0603")
      (libsource (lib "eagle-import") (part "1.5KOHM-0603-1/10W-1%"))
    )
    (comp (ref "R46")
      (value "0")
      (footprint "eagle-import:0603")
      (libsource (lib "eagle-import") (part "1.5KOHM-0603-1/10W-1%"))
    )
    (comp (ref "C1")
      (value "0.1uF")
      (footprint "eagle-import:C0805K")
      (libsource (lib "eagle-import") (part "rcl_334_C-EUC0805K"))
    )
    (comp (ref "C2")
      (value "10uF/25V/X5R")
      (footprint "eagle-import:C1210K")
      (libsource (lib "eagle-import") (part "rcl_334_C-EUC1210K"))
    )
    (comp (ref "C3")
      (value "10uF/25V/X5R")
      (footprint "eagle-import:C0805")
      (libsource (lib "eagle-import") (part "rcl_334_C-EUC0805"))
    )
    (comp (ref "C5")
      (value "1uF/25V")
      (footprint "eagle-import:C0805K")
      (libsource (lib "eagle-import") (part "rcl_334_C-EUC0805K"))
    )
    (comp (ref "C6")
      (value "0.1uF")
      (footprint "eagle-import:C0603")
      (libsource (lib "eagle-import") (part "rcl_334_C-EUC0603"))
    )
    (comp (ref "C7")
      (value "10uF/25V/X5R")
      (footprint "eagle-import:C1210K")
      (libsource (lib "eagle-import") (part "rcl_334_C-EUC1210K"))
    )
    (comp (ref "C8")
      (value "10uF/25V/X5R")
      (footprint "eagle-import:C0603")
      (libsource (lib "eagle-import") (part "rcl_334_C-EUC0603"))
    )
    (comp (ref "C9")
      (value "1uF/25V")
      (footprint "eagle-import:C0805K")
      (libsource (lib "eagle-import") (part "rcl_334_C-EUC0805K"))
    )
    (comp (ref "C10")
      (value "0.1uF")
      (footprint "eagle-import:C0603")
      (libsource (lib "eagle-import") (part "rcl_334_C-EUC0603"))
    )
    (comp (ref "C11")
      (value "10uF/25V/X5R")
      (footprint "eagle-import:C1210K")
      (libsource (lib "eagle-import") (part "rcl_334_C-EUC1210K"))
    )
    (comp (ref "C39")
      (value "10nF")
      (footprint "eagle-import:C0603")
      (libsource (lib "eagle-import") (part "rcl_334_C-EUC0603"))
    )
    (comp (ref "D2")
      (value "250mA/100V")
      (footprint "eagle-import:SOD-323")
      (libsource (lib "eagle-import") (part "DIODE-BAS16J"))
    )
    (comp (ref "D3")
      (value "250mA/100V")
      (footprint "eagle-import:SOD-323")
      (libsource (lib "eagle-import") (part "DIODE-BAS16J"))
    )
    (comp (ref "D4")
      (value "250mA/100V")
      (footprint "eagle-import:SOD-323")
      (libsource (lib "eagle-import") (part "DIODE-BAS16J"))
    )
    (comp (ref "D6")
      (value "GREEN")
      (footprint "eagle-import:LED-0603")
      (libsource (lib "eagle-import") (part "LED-GREEN0603"))
    )
    (comp (ref "D7")
      (value "GREEN")
      (footprint "eagle-import:LED-0603")
      (libsource (lib "eagle-import") (part "LED-GREEN0603"))
    )
    (comp (ref "D8")
      (value "GREEN")
      (footprint "eagle-import:LED-0603")
      (libsource (lib "eagle-import") (part "LED-GREEN0603"))
    )
    (comp (ref "D15")
      (value "1A/23V/620mV")
      (footprint "eagle-import:SOD-323")
      (libsource (lib "eagle-import") (part "DIODE-SCHOTTKY-BAT20J"))
    )
    (comp (ref "D17")
      (value "250mA/100V")
      (footprint "eagle-import:SOD-323")
      (libsource (lib "eagle-import") (part "DIODE-BAS16J"))
    )
    (comp (ref "R3")
      (value "240")
      (footprint "eagle-import:0603")
      (libsource (lib "eagle-import") (part "1.5KOHM-0603-1/10W-1%"))
    )
    (comp (ref "R4")
      (value "1.5k")
      (footprint "eagle-import:0603")
      (libsource (lib "eagle-import") (part "1.5KOHM-0603-1/10W-1%"))
    )
    (comp (ref "R5")
      (value "240")
      (footprint "eagle-import:0603")
      (libsource (lib "eagle-import") (part "1.5KOHM-0603-1/10W-1%"))
    )
    (comp (ref "R6")
      (value "390")
      (footprint "eagle-import:0603")
      (libsource (lib "eagle-import") (part "1.5KOHM-0603-1/10W-1%"))
    )
    (comp (ref "R7")
      (value "0")
      (footprint "eagle-import:1210")
      (libsource (lib "eagle-import") (part "0.1OHM-1210-1/2W-1%"))
    )
    (comp (ref "R8")
      (value "5.6k")
      (footprint "eagle-import:0603")
      (libsource (lib "eagle-import") (part "1.5KOHM-0603-1/10W-1%"))
    )
    (comp (ref "R9")
      (value "3.7k")
      (footprint "eagle-import:0603")
      (libsource (lib "eagle-import") (part "1.5KOHM-0603-1/10W-1%"))
    )
    (comp (ref "R10")
      (value "750")
      (footprint "eagle-import:0603")
      (libsource (lib "eagle-import") (part "1.5KOHM-0603-1/10W-1%"))
    )
    (comp (ref "U1")
      (value "V_REG_317SINK")
      (footprint "eagle-import:TO220-ADJ")
      (libsource (lib "eagle-import") (part "V_REG_317SINK"))
    )
    (comp (ref "U2")
      (value "V_REG_317SINK")
      (footprint "eagle-import:TO220-ADJ")
      (libsource (lib "eagle-import") (part "V_REG_317SINK"))
    )
  )
  (nets
    (net (code "1") (name "ADJ33") (class "Default")
      (node (ref "C10") (pin "1") (pinfunction "1_1") (pintype "passive"))
      (node (ref "C8") (pin "1") (pinfunction "1_1") (pintype "passive"))
      (node (ref "D3") (pin "A") (pinfunction "A_A") (pintype "passive"))
      (node (ref "R5") (pin "1") (pinfunction "1_1") (pintype "passive"))
      (node (ref "R6") (pin "2") (pinfunction "2_2") (pintype "passive"))
      (node (ref "U2") (pin "ADJ") (pinfunction "ADJ_ADJ") (pintype "input"))
    )
    (net (code "2") (name "ADJ90") (class "Default")
      (node (ref "C3") (pin "1") (pinfunction "1_1") (pintype "passive"))
      (node (ref "C6") (pin "1") (pinfunction "1_1") (pintype "passive"))
      (node (ref "D4") (pin "A") (pinfunction "A_A") (pintype "passive"))
      (node (ref "R3") (pin "1") (pinfunction "1_1") (pintype "passive"))
      (node (ref "R4") (pin "2") (pinfunction "2_2") (pintype "passive"))
      (node (ref "U1") (pin "ADJ") (pinfunction "ADJ_ADJ") (pintype "input"))
    )
    (net (code "3") (name "AMP_DAC1_OUT") (class "Default")
      (node (ref "R31") (pin "1") (pinfunction "1_1") (pintype "passive"))
      (node (ref "U3") (pin "10") (pinfunction "IO25_10") (pintype "bidirectional"))
    )
    (net (code "4") (name "BAT_ADC_IN") (class "Default")
      (node (ref "R20") (pin "1") (pinfunction "1_1") (pintype "passive"))
      (node (ref "U3") (pin "6") (pinfunction "IO34_6") (pintype "bidirectional"))
    )
    (net (code "5") (name "BAT_OP_IN") (class "Default")
      (node (ref "D12") (pin "C") (pinfunction "C_C") (pintype "passive"))
      (node (ref "IC3") (pin "1") (pinfunction "+IN_1") (pintype "input"))
      (node (ref "R32") (pin "1") (pinfunction "1_1") (pintype "passive"))
      (node (ref "R33") (pin "2") (pinfunction "2_2") (pintype "passive"))
    )
    (net (code "6") (name "BAT_OP_OUT") (class "Default")
      (node (ref "IC3") (pin "3") (pinfunction "-IN_3") (pintype "input"))
      (node (ref "IC3") (pin "4") (pinfunction "OUT_4") (pintype "output"))
      (node (ref "R20") (pin "2") (pinfunction "2_2") (pintype "passive"))
    )
    (net (code "7") (name "CLK") (class "Default")
      (node (ref "U3") (pin "20") (pinfunction "CLK_20") (pintype "bidirectional"))
    )
    (net (code "8") (name "CMD") (class "Default")
      (node (ref "U3") (pin "19") (pinfunction "CMD_19") (pintype "bidirectional"))
    )
    (net (code "9") (name "D6ANODE") (class "Default")
      (node (ref "C39") (pin "2") (pinfunction "2_2") (pintype "passive"))
      (node (ref "D6") (pin "A") (pinfunction "A_A") (pintype "passive"))
      (node (ref "R8") (pin "2") (pinfunction "2_2") (pintype "passive"))
    )
    (net (code "10") (name "D7ANODE") (class "Default")
      (node (ref "D7") (pin "A") (pinfunction "A_A") (pintype "passive"))
      (node (ref "R9") (pin "2") (pinfunction "2_2") (pintype "passive"))
    )
    (net (code "11") (name "D8ANODE") (class "Default")
      (node (ref "D8") (pin "A") (pinfunction "A_A") (pintype "passive"))
      (node (ref "R10") (pin "2") (pinfunction "2_2") (pintype "passive"))
    )
    (net (code "12") (name "DAC_OP_OUT") (class "Default")
      (node (ref "IC6") (pin "3") (pinfunction "-IN_3") (pintype "input"))
      (node (ref "IC6") (pin "4") (pinfunction "OUT_4") (pintype "output"))
      (node (ref "R40") (pin "2") (pinfunction "2_2") (pintype "passive"))
    )
    (net (code "13") (name "DAC_OUT_OP_IN") (class "Default")
      (node (ref "D13") (pin "C") (pinfunction "C_C") (pintype "passive"))
      (node (ref "IC6") (pin "1") (pinfunction "+IN_1") (pintype "input"))
      (node (ref "R38") (pin "1") (pinfunction "1_1") (pintype "passive"))
      (node (ref "R39") (pin "2") (pinfunction "2_2") (pintype "passive"))
    )
    (net (code "14") (name "DTR") (class "Default")
      (node (ref "Q2") (pin "1") (pinfunction "E_1") (pintype "passive"))
      (node (ref "R41") (pin "2") (pinfunction "2_2") (pintype "passive"))
      (node (ref "U4") (pin "1") (pinfunction "~{DTR}_1") (pintype "bidirectional"))
    )
    (net (code "15") (name "EN") (class "Default")
      (node (ref "Q2") (pin "3") (pinfunction "C_3") (pintype "passive"))
      (node (ref "R2") (pin "1") (pinfunction "1_1") (pintype "passive"))
      (node (ref "SW2") (pin "2") (pinfunction "2_2") (pintype "bidirectional"))
      (node (ref "U3") (pin "3") (pinfunction "EN_3") (pintype "bidirectional"))
    )
    (net (code "16") (name "FT232_RXD") (class "Default")
      (node (ref "R45") (pin "1") (pinfunction "1_1") (pintype "passive"))
      (node (ref "R48") (pin "1") (pinfunction "1_1") (pintype "passive"))
      (node (ref "U4") (pin "4") (pinfunction "RXD_4") (pintype "bidirectional"))
    )
    (net (code "17") (name "FT232_TXD") (class "Default")
      (node (ref "R44") (pin "1") (pinfunction "1_1") (pintype "passive"))
      (node (ref "R47") (pin "1") (pinfunction "1_1") (pintype "passive"))
      (node (ref "U4") (pin "20") (pinfunction "TXD_20") (pintype "bidirectional"))
    )
    (net (code "18") (name "GND") (class "Default")
      (node (ref "C1") (pin "2") (pinfunction "2_2") (pintype "passive"))
      (node (ref "C10") (pin "2") (pinfunction "2_2") (pintype "passive"))
      (node (ref "C11") (pin "2") (pinfunction "2_2") (pintype "passive"))
      (node (ref "C12") (pin "2") (pinfunction "2_2") (pintype "passive"))
      (node (ref "C13") (pin "2") (pinfunction "2_2") (pintype "passive"))
      (node (ref "C14") (pin "2") (pinfunction "2_2") (pintype "passive"))
      (node (ref "C15") (pin "2") (pinfunction "2_2") (pintype "passive"))
      (node (ref "C16") (pin "2") (pinfunction "2_2") (pintype "passive"))
      (node (ref "C17") (pin "2") (pinfunction "2_2") (pintype "passive"))
      (node (ref "C18") (pin "-") (pinfunction "-_-") (pintype "passive"))
      (node (ref "C19") (pin "2") (pinfunction "2_2") (pintype "passive"))
      (node (ref "C2") (pin "2") (pinfunction "2_2") (pintype "passive"))
      (node (ref "C20") (pin "2") (pinfunction "2_2") (pintype "passive"))
      (node (ref "C21") (pin "2") (pinfunction "2_2") (pintype "passive"))
      (node (ref "C22") (pin "2") (pinfunction "2_2") (pintype "passive"))
      (node (ref "C23") (pin "2") (pinfunction "2_2") (pintype "passive"))
      (node (ref "C24") (pin "2") (pinfunction "2_2") (pintype "passive"))
      (node (ref "C25") (pin "2") (pinfunction "2_2") (pintype "passive"))
      (node (ref "C26") (pin "2") (pinfunction "2_2") (pintype "passive"))
      (node (ref "C27") (pin "2") (pinfunction "2_2") (pintype "passive"))
      (node (ref "C28") (pin "2") (pinfunction "2_2") (pintype "passive"))
      (node (ref "C29") (pin "1") (pinfunction "1_1") (pintype "passive"))
      (node (ref "C3") (pin "2") (pinfunction "2_2") (pintype "passive"))
      (node (ref "C30") (pin "2") (pinfunction "2_2") (pintype "passive"))
      (node (ref "C31") (pin "2") (pinfunction "2_2") (pintype "passive"))
      (node (ref "C32") (pin "2") (pinfunction "2_2") (pintype "passive"))
      (node (ref "C33") (pin "1") (pinfunction "1_1") (pintype "passive"))
      (node (ref "C34") (pin "2") (pinfunction "2_2") (pintype "passive"))
      (node (ref "C36") (pin "2") (pinfunction "2_2") (pintype "passive"))
      (node (ref "C37") (pin "2") (pinfunction "2_2") (pintype "passive"))
      (node (ref "C38") (pin "2") (pinfunction "2_2") (pintype "passive"))
      (node (ref "C39") (pin "1") (pinfunction "1_1") (pintype "passive"))
      (node (ref "C4") (pin "2") (pinfunction "2_2") (pintype "passive"))
      (node (ref "C5") (pin "2") (pinfunction "2_2") (pintype "passive"))
      (node (ref "C6") (pin "2") (pinfunction "2_2") (pintype "passive"))
      (node (ref "C7") (pin "2") (pinfunction "2_2") (pintype "passive"))
      (node (ref "C8") (pin "2") (pinfunction "2_2") (pintype "passive"))
      (node (ref "C9") (pin "2") (pinfunction "2_2") (pintype "passive"))
      (node (ref "D12") (pin "A") (pinfunction "A_A") (pintype "passive"))
      (node (ref "D13") (pin "A") (pinfunction "A_A") (pintype "passive"))
      (node (ref "D16") (pin "A") (pinfunction "A_A") (pintype "passive"))
      (node (ref "D18") (pin "A") (pinfunction "A_A") (pintype "passive"))
      (node (ref "D19") (pin "A") (pinfunction "A_A") (pintype "passive"))
      (node (ref "D5") (pin "A") (pinfunction "A_A") (pintype "passive"))
      (node (ref "D6") (pin "C") (pinfunction "C_C") (pintype "passive"))
      (node (ref "D7") (pin "C") (pinfunction "C_C") (pintype "passive"))
      (node (ref "D8") (pin "C") (pinfunction "C_C") (pintype "passive"))
      (node (ref "IC1") (pin "2") (pinfunction "V-_2") (pintype "power_in"))
      (node (ref "IC2") (pin "4") (pinfunction "V-_4") (pintype "power_in"))
      (node (ref "IC3") (pin "2") (pinfunction "V-_2") (pintype "power_in"))
      (node (ref "IC6") (pin "2") (pinfunction "V-_2") (pintype "power_in"))
      (node (ref "J1") (pin "2") (pinfunction "2_2") (pintype "passive"))
      (node (ref "J2") (pin "2") (pinfunction "2_2") (pintype "passive"))
      (node (ref "J2") (pin "4") (pinfunction "4_4") (pintype "passive"))
      (node (ref "J3") (pin "GND") (pinfunction "GND_GND") (pintype "power_in"))
      (node (ref "J3") (pin "SHLD1") (pinfunction "SHIELD_SHLD1") (pintype "bidirectional"))
      (node (ref "J3") (pin "SHLD2") (pinfunction "SHIELD_SHLD2") (pintype "bidirectional"))
      (node (ref "J4") (pin "1") (pinfunction "1_1") (pintype "passive"))
      (node (ref "J5") (pin "2") (pinfunction "2_2") (pintype "passive"))
      (node (ref "Q1") (pin "2") (pinfunction "S_2") (pintype "passive"))
      (node (ref "Q3") (pin "2") (pinfunction "S_2") (pintype "bidirectional"))
      (node (ref "R11") (pin "2") (pinfunction "2_2") (pintype "passive"))
      (node (ref "R14") (pin "1") (pinfunction "1_1") (pintype "passive"))
      (node (ref "R33") (pin "1") (pinfunction "1_1") (pintype "passive"))
      (node (ref "R39") (pin "1") (pinfunction "1_1") (pintype "passive"))
      (node (ref "R4") (pin "1") (pinfunction "1_1") (pintype "passive"))
      (node (ref "R52") (pin "2") (pinfunction "2_2") (pintype "passive"))
      (node (ref "R53") (pin "2") (pinfunction "2_2") (pintype "passive"))
      (node (ref "R6") (pin "1") (pinfunction "1_1") (pintype "passive"))
      (node (ref "S1") (pin "C") (pinfunction "C_C") (pintype "bidirectional"))
      (node (ref "S1") (pin "SW-") (pinfunction "SW-_SW-") (pintype "bidirectional"))
      (node (ref "S2") (pin "1") (pinfunction "1_1") (pintype "passive"))
      (node (ref "SW1") (pin "1") (pinfunction "1_1") (pintype "bidirectional"))
      (node (ref "SW2") (pin "1") (pinfunction "1_1") (pintype "bidirectional"))
      (node (ref "U3") (pin "1") (pinfunction "GND_1") (pintype "bidirectional"))
      (node (ref "U3") (pin "15") (pinfunction "GND_15") (pintype "bidirectional"))
      (node (ref "U3") (pin "24") (pinfunction "IO2_24") (pintype "bidirectional"))
      (node (ref "U3") (pin "38") (pinfunction "GND_38") (pintype "bidirectional"))
      (node (ref "U3") (pin "GND") (pinfunction "GND_GND") (pintype "bidirectional"))
      (node (ref "U4") (pin "16") (pinfunction "GND_16") (pintype "bidirectional"))
      (node (ref "U4") (pin "6") (pinfunction "GND_6") (pintype "bidirectional"))
      (node (ref "U5") (pin "4") (pinfunction "GND_4") (pintype "passive"))
      (node (ref "U7") (pin "2") (pinfunction "GND_2") (pintype "input"))
    )
    (net (code "19") (name "GND_IN") (class "Default")
      (node (ref "J7") (pin "6") (pinfunction "6_6") (pintype "passive"))
      (node (ref "Q1") (pin "3") (pinfunction "D_3") (pintype "passive"))
    )
    (net (code "20") (name "IO0") (class "Default")
      (node (ref "R1") (pin "1") (pinfunction "1_1") (pintype "passive"))
      (node (ref "R43") (pin "1") (pinfunction "1_1") (pintype "passive"))
      (node (ref "SW1") (pin "2") (pinfunction "2_2") (pintype "bidirectional"))
      (node (ref "U3") (pin "25") (pinfunction "IO0_25") (pintype "bidirectional"))
    )
    (net (code "21") (name "IO4") (class "Default")
      (node (ref "U3") (pin "26") (pinfunction "IO4_26") (pintype "bidirectional"))
    )
    (net (code "22") (name "IO5") (class "Default")
      (node (ref "U3") (pin "29") (pinfunction "IO5_29") (pintype "bidirectional"))
    )
    (net (code "23") (name "IO8") (class "Default")
      (node (ref "U3") (pin "22") (pinfunction "SD1_22") (pintype "bidirectional"))
    )
    (net (code "24") (name "IO12") (class "Default")
      (node (ref "U3") (pin "14") (pinfunction "IO12_14") (pintype "bidirectional"))
    )
    (net (code "25") (name "IO13") (class "Default")
      (node (ref "U3") (pin "16") (pinfunction "IO13_16") (pintype "bidirectional"))
    )
    (net (code "26") (name "IO15") (class "Default")
      (node (ref "U3") (pin "23") (pinfunction "IO15_23") (pintype "bidirectional"))
    )
    (net (code "27") (name "IO19") (class "Default")
      (node (ref "U3") (pin "31") (pinfunction "IO19_31") (pintype "bidirectional"))
    )
    (net (code "28") (name "IO21") (class "Default")
      (node (ref "U3") (pin "33") (pinfunction "IO21_33") (pintype "bidirectional"))
    )
    (net (code "29") (name "IO23") (class "Default")
      (node (ref "U3") (pin "37") (pinfunction "IO23_37") (pintype "bidirectional"))
    )
    (net (code "30") (name "IO32") (class "Default")
      (node (ref "R55") (pin "2") (pinfunction "2_2") (pintype "passive"))
      (node (ref "U3") (pin "8") (pinfunction "IO32_8") (pintype "bidirectional"))
    )
    (net (code "31") (name "IO33") (class "Default")
      (node (ref "R56") (pin "2") (pinfunction "2_2") (pintype "passive"))
      (node (ref "U3") (pin "9") (pinfunction "IO33_9") (pintype "bidirectional"))
    )
    (net (code "32") (name "IO36") (class "Default")
      (node (ref "U3") (pin "4") (pinfunction "SENSOR_VP_4") (pintype "bidirectional"))
    )
    (net (code "33") (name "IO39") (class "Default")
      (node (ref "U3") (pin "5") (pinfunction "SENSOR_VN_5") (pintype "bidirectional"))
    )
    (net (code "34") (name "LM321_IN+") (class "Default")
      (node (ref "C12") (pin "1") (pinfunction "1_1") (pintype "passive"))
      (node (ref "IC1") (pin "1") (pinfunction "+IN_1") (pintype "input"))
      (node (ref "R31") (pin "2") (pinfunction "2_2") (pintype "passive"))
    )
    (net (code "35") (name "LM321_IN-") (class "Default")
      (node (ref "C21") (pin "1") (pinfunction "1_1") (pintype "passive"))
      (node (ref "IC1") (pin "3") (pinfunction "-IN_3") (pintype "input"))
      (node (ref "R11") (pin "1") (pinfunction "1_1") (pintype "passive"))
      (node (ref "R12") (pin "1") (pinfunction "1_1") (pintype "passive"))
    )
    (net (code "36") (name "LM321_OUT") (class "Default")
      (node (ref "IC1") (pin "4") (pinfunction "OUT_4") (pintype "output"))
      (node (ref "R12") (pin "2") (pinfunction "2_2") (pintype "passive"))
      (node (ref "R15") (pin "1") (pinfunction "1_1") (pintype "passive"))
    )
    (net (code "37") (name "LTC2950_EN") (class "Default")
      (node (ref "D16") (pin "C") (pinfunction "C_C") (pintype "passive"))
      (node (ref "Q3") (pin "1") (pinfunction "G_1") (pintype "bidirectional"))
      (node (ref "R50") (pin "1") (pinfunction "1_1") (pintype "passive"))
      (node (ref "U5") (pin "6") (pinfunction "EN/~{EN}_6") (pintype "output"))
    )
    (net (code "38") (name "MIC5219_IN") (class "Default")
      (node (ref "C38") (pin "1") (pinfunction "1_1") (pintype "passive"))
      (node (ref "D11") (pin "C") (pinfunction "C_C") (pintype "passive"))
      (node (ref "U7") (pin "1") (pinfunction "IN_1") (pintype "input"))
      (node (ref "U7") (pin "3") (pinfunction "EN_3") (pintype "input"))
    )
    (net (code "39") (name "MIC5219_V33") (class "Default")
      (node (ref "C19") (pin "1") (pinfunction "1_1") (pintype "passive"))
      (node (ref "R49") (pin "1") (pinfunction "1_1") (pintype "passive"))
      (node (ref "U7") (pin "5") (pinfunction "OUT_5") (pintype "passive"))
    )
    (net (code "40") (name "MIC_BYPASS") (class "Default")
      (node (ref "C37") (pin "1") (pinfunction "1_1") (pintype "passive"))
      (node (ref "U7") (pin "4") (pinfunction "BP_4") (pintype "input"))
    )
    (net (code "41") (name "Net-(IC2-ILIM)") (class "Default")
      (node (ref "IC2") (pin "3") (pinfunction "ILIM_3") (pintype "input"))
      (node (ref "R14") (pin "2") (pinfunction "2_2") (pintype "passive"))
    )
    (net (code "42") (name "Net-(Q2A-B)") (class "Default")
      (node (ref "Q2") (pin "5") (pinfunction "B_5") (pintype "passive"))
      (node (ref "R41") (pin "1") (pinfunction "1_1") (pintype "passive"))
    )
    (net (code "43") (name "Net-(Q2B-B)") (class "Default")
      (node (ref "Q2") (pin "2") (pinfunction "B_2") (pintype "passive"))
      (node (ref "R42") (pin "1") (pinfunction "1_1") (pintype "passive"))
    )
    (net (code "44") (name "OFFT") (class "Default")
      (node (ref "C31") (pin "1") (pinfunction "1_1") (pintype "passive"))
      (node (ref "U5") (pin "7") (pinfunction "OFFT_7") (pintype "input"))
    )
    (net (code "45") (name "ONT") (class "Default")
      (node (ref "C27") (pin "1") (pinfunction "1_1") (pintype "passive"))
      (node (ref "U5") (pin "3") (pinfunction "ONT_3") (pintype "input"))
    )
    (net (code "46") (name "OPA548_IN+") (class "Default")
      (node (ref "C13") (pin "1") (pinfunction "1_1") (pintype "passive"))
      (node (ref "IC2") (pin "1") (pinfunction "+IN_1") (pintype "input"))
      (node (ref "R15") (pin "2") (pinfunction "2_2") (pintype "passive"))
    )
    (net (code "47") (name "OPA548_IN-") (class "Default")
      (node (ref "C30") (pin "1") (pinfunction "1_1") (pintype "passive"))
      (node (ref "IC2") (pin "2") (pinfunction "-IN_2") (pintype "input"))
      (node (ref "R16") (pin "1") (pinfunction "1_1") (pintype "passive"))
    )
    (net (code "48") (name "OPA548_OUT") (class "Default")
      (node (ref "IC2") (pin "6") (pinfunction "OUT_6") (pintype "output"))
      (node (ref "R16") (pin "2") (pinfunction "2_2") (pintype "passive"))
      (node (ref "R17") (pin "1") (pinfunction "1_1") (pintype "passive"))
      (node (ref "R38") (pin "2") (pinfunction "2_2") (pintype "passive"))
    )
    (net (code "49") (name "OPA548_STAT") (class "Default")
      (node (ref "IC2") (pin "7") (pinfunction "E/S_7") (pintype "bidirectional"))
      (node (ref "R13") (pin "1") (pinfunction "1_1") (pintype "passive"))
      (node (ref "U3") (pin "13") (pinfunction "IO14_13") (pintype "bidirectional"))
    )
    (net (code "50") (name "OUT_ADC_IN") (class "Default")
      (node (ref "R40") (pin "1") (pinfunction "1_1") (pintype "passive"))
      (node (ref "U3") (pin "7") (pinfunction "IO35_7") (pintype "bidirectional"))
    )
    (net (code "51") (name "Q2Q2D") (class "Default")
      (node (ref "Q2") (pin "6") (pinfunction "C_6") (pintype "passive"))
      (node (ref "R43") (pin "2") (pinfunction "2_2") (pintype "passive"))
    )
    (net (code "52") (name "Q3D") (class "Default")
      (node (ref "Q3") (pin "3") (pinfunction "D_3") (pintype "bidirectional"))
      (node (ref "R34") (pin "2") (pinfunction "2_2") (pintype "passive"))
    )
    (net (code "53") (name "Q4G") (class "Default")
      (node (ref "D9") (pin "A") (pinfunction "A_A") (pintype "passive"))
      (node (ref "Q4") (pin "1") (pinfunction "G_1") (pintype "bidirectional"))
      (node (ref "R53") (pin "1") (pinfunction "1_1") (pintype "passive"))
    )
    (net (code "54") (name "Q5G") (class "Default")
      (node (ref "C33") (pin "2") (pinfunction "2_2") (pintype "passive"))
      (node (ref "C35") (pin "2") (pinfunction "2_2") (pintype "passive"))
      (node (ref "C42") (pin "1") (pinfunction "1_1") (pintype "passive"))
      (node (ref "D10") (pin "A") (pinfunction "A_A") (pintype "passive"))
      (node (ref "Q5") (pin "1") (pinfunction "G_1") (pintype "bidirectional"))
      (node (ref "R51") (pin "1") (pinfunction "1_1") (pintype "passive"))
    )
    (net (code "55") (name "Q5G_1") (class "Default")
      (node (ref "R34") (pin "1") (pinfunction "1_1") (pintype "passive"))
      (node (ref "R51") (pin "2") (pinfunction "2_2") (pintype "passive"))
      (node (ref "R54") (pin "2") (pinfunction "2_2") (pintype "passive"))
    )
    (net (code "56") (name "ROTA") (class "Default")
      (node (ref "R25") (pin "1") (pinfunction "1_1") (pintype "passive"))
      (node (ref "U3") (pin "27") (pinfunction "IO16_27") (pintype "bidirectional"))
    )
    (net (code "57") (name "ROTA_S1") (class "Default")
      (node (ref "J2") (pin "1") (pinfunction "1_1") (pintype "passive"))
      (node (ref "R22") (pin "1") (pinfunction "1_1") (pintype "passive"))
      (node (ref "R25") (pin "2") (pinfunction "2_2") (pintype "passive"))
      (node (ref "S1") (pin "A") (pinfunction "A_A") (pintype "bidirectional"))
    )
    (net (code "58") (name "ROTB") (class "Default")
      (node (ref "R24") (pin "1") (pinfunction "1_1") (pintype "passive"))
      (node (ref "U3") (pin "28") (pinfunction "IO17_28") (pintype "bidirectional"))
    )
    (net (code "59") (name "ROTB_S1") (class "Default")
      (node (ref "J2") (pin "3") (pinfunction "3_3") (pintype "passive"))
      (node (ref "R21") (pin "1") (pinfunction "1_1") (pintype "passive"))
      (node (ref "R24") (pin "2") (pinfunction "2_2") (pintype "passive"))
      (node (ref "S1") (pin "B") (pinfunction "B_B") (pintype "bidirectional"))
    )
    (net (code "60") (name "ROTP") (class "Default")
      (node (ref "R26") (pin "2") (pinfunction "2_2") (pintype "passive"))
      (node (ref "U3") (pin "30") (pinfunction "IO18_30") (pintype "bidirectional"))
    )
    (net (code "61") (name "ROTP_S1") (class "Default")
      (node (ref "J2") (pin "5") (pinfunction "5_5") (pintype "passive"))
      (node (ref "R23") (pin "1") (pinfunction "1_1") (pintype "passive"))
      (node (ref "R26") (pin "1") (pinfunction "1_1") (pintype "passive"))
      (node (ref "S1") (pin "SW+") (pinfunction "SW+_SW+") (pintype "bidirectional"))
    )
    (net (code "62") (name "RTS") (class "Default")
      (node (ref "Q2") (pin "4") (pinfunction "E_4") (pintype "passive"))
      (node (ref "R42") (pin "2") (pinfunction "2_2") (pintype "passive"))
      (node (ref "U4") (pin "2") (pinfunction "~{RTS}_2") (pintype "bidirectional"))
    )
    (net (code "63") (name "RTS0") (class "Default")
      (node (ref "U3") (pin "36") (pinfunction "IO22_36") (pintype "bidirectional"))
    )
    (net (code "64") (name "RX") (class "Default")
      (node (ref "D1") (pin "-") (pinfunction "-_-") (pintype "passive"))
      (node (ref "J7") (pin "3") (pinfunction "3_3") (pintype "passive"))
    )
    (net (code "65") (name "RXD0") (class "Default")
      (node (ref "D1") (pin "+") (pinfunction "+_+") (pintype "passive"))
      (node (ref "R45") (pin "2") (pinfunction "2_2") (pintype "passive"))
      (node (ref "R47") (pin "2") (pinfunction "2_2") (pintype "passive"))
      (node (ref "U3") (pin "34") (pinfunction "RXD0_34") (pintype "bidirectional"))
    )
    (net (code "66") (name "SCL") (class "Default")
      (node (ref "J4") (pin "3") (pinfunction "3_3") (pintype "passive"))
      (node (ref "R30") (pin "2") (pinfunction "2_2") (pintype "passive"))
      (node (ref "U3") (pin "12") (pinfunction "IO27_12") (pintype "bidirectional"))
    )
    (net (code "67") (name "SD2") (class "Default")
      (node (ref "U3") (pin "17") (pinfunction "SD2_17") (pintype "bidirectional"))
    )
    (net (code "68") (name "SD3") (class "Default")
      (node (ref "U3") (pin "18") (pinfunction "SD3_18") (pintype "bidirectional"))
    )
    (net (code "69") (name "SDA") (class "Default")
      (node (ref "J4") (pin "4") (pinfunction "4_4") (pintype "passive"))
      (node (ref "R29") (pin "2") (pinfunction "2_2") (pintype "passive"))
      (node (ref "U3") (pin "11") (pinfunction "IO26_11") (pintype "bidirectional"))
    )
    (net (code "70") (name "SDO") (class "Default")
      (node (ref "U3") (pin "21") (pinfunction "SDO_21") (pintype "bidirectional"))
    )
    (net (code "71") (name "TXD0") (class "Default")
      (node (ref "J7") (pin "2") (pinfunction "2_2") (pintype "passive"))
      (node (ref "R44") (pin "2") (pinfunction "2_2") (pintype "passive"))
      (node (ref "R48") (pin "2") (pinfunction "2_2") (pintype "passive"))
      (node (ref "U3") (pin "35") (pinfunction "TXD0_35") (pintype "bidirectional"))
    )
    (net (code "72") (name "USBDM") (class "Default")
      (node (ref "R27") (pin "1") (pinfunction "1_1") (pintype "passive"))
      (node (ref "U4") (pin "12") (pinfunction "USBDM_12") (pintype "bidirectional"))
    )
    (net (code "73") (name "USBDP") (class "Default")
      (node (ref "R28") (pin "2") (pinfunction "2_2") (pintype "passive"))
      (node (ref "U4") (pin "11") (pinfunction "USBDP_11") (pintype "bidirectional"))
    )
    (net (code "74") (name "USBM") (class "Default")
      (node (ref "J3") (pin "D-") (pinfunction "D-_D-") (pintype "bidirectional"))
      (node (ref "R27") (pin "2") (pinfunction "2_2") (pintype "passive"))
    )
    (net (code "75") (name "USBP") (class "Default")
      (node (ref "J3") (pin "D+") (pinfunction "D+_D+") (pintype "bidirectional"))
      (node (ref "R28") (pin "1") (pinfunction "1_1") (pintype "passive"))
    )
    (net (code "76") (name "V33") (class "Default")
      (node (ref "C11") (pin "1") (pinfunction "1_1") (pintype "passive"))
      (node (ref "C23") (pin "1") (pinfunction "1_1") (pintype "passive"))
      (node (ref "C29") (pin "2") (pinfunction "2_2") (pintype "passive"))
      (node (ref "C32") (pin "1") (pinfunction "1_1") (pintype "passive"))
      (node (ref "C36") (pin "1") (pinfunction "1_1") (pintype "passive"))
      (node (ref "C4") (pin "1") (pinfunction "1_1") (pintype "passive"))
      (node (ref "D15") (pin "C") (pinfunction "C_C") (pintype "passive"))
      (node (ref "IC3") (pin "5") (pinfunction "V+_5") (pintype "power_in"))
      (node (ref "IC6") (pin "5") (pinfunction "V+_5") (pintype "power_in"))
      (node (ref "J4") (pin "2") (pinfunction "2_2") (pintype "passive"))
      (node (ref "J7") (pin "4") (pinfunction "4_4") (pintype "passive"))
      (node (ref "Q1") (pin "1") (pinfunction "G_1") (pintype "passive"))
      (node (ref "R1") (pin "2") (pinfunction "2_2") (pintype "passive"))
      (node (ref "R13") (pin "2") (pinfunction "2_2") (pintype "passive"))
      (node (ref "R2") (pin "2") (pinfunction "2_2") (pintype "passive"))
      (node (ref "R21") (pin "2") (pinfunction "2_2") (pintype "passive"))
      (node (ref "R22") (pin "2") (pinfunction "2_2") (pintype "passive"))
      (node (ref "R23") (pin "2") (pinfunction "2_2") (pintype "passive"))
      (node (ref "R29") (pin "1") (pinfunction "1_1") (pintype "passive"))
      (node (ref "R30") (pin "1") (pinfunction "1_1") (pintype "passive"))
      (node (ref "R49") (pin "2") (pinfunction "2_2") (pintype "passive"))
      (node (ref "U3") (pin "2") (pinfunction "3V3_2") (pintype "bidirectional"))
    )
    (net (code "77") (name "V36") (class "Default")
      (node (ref "C9") (pin "1") (pinfunction "1_1") (pintype "passive"))
      (node (ref "D15") (pin "A") (pinfunction "A_A") (pintype "passive"))
      (node (ref "D2") (pin "A") (pinfunction "A_A") (pintype "passive"))
      (node (ref "D3") (pin "C") (pinfunction "C_C") (pintype "passive"))
      (node (ref "R10") (pin "1") (pinfunction "1_1") (pintype "passive"))
      (node (ref "R5") (pin "2") (pinfunction "2_2") (pintype "passive"))
      (node (ref "U2") (pin "OUT") (pinfunction "OUT_OUT") (pintype "output"))
    )
    (net (code "78") (name "V90") (class "Default")
      (node (ref "C5") (pin "1") (pinfunction "1_1") (pintype "passive"))
      (node (ref "D17") (pin "A") (pinfunction "A_A") (pintype "passive"))
      (node (ref "D4") (pin "C") (pinfunction "C_C") (pintype "passive"))
      (node (ref "R3") (pin "2") (pinfunction "2_2") (pintype "passive"))
      (node (ref "R7") (pin "1") (pinfunction "1_1") (pintype "passive"))
      (node (ref "R9") (pin "1") (pinfunction "1_1") (pintype "passive"))
      (node (ref "U1") (pin "OUT") (pinfunction "OUT_OUT") (pintype "output"))
    )
    (net (code "79") (name "V90IN") (class "Default")
      (node (ref "C7") (pin "1") (pinfunction "1_1") (pintype "passive"))
      (node (ref "D2") (pin "C") (pinfunction "C_C") (pintype "passive"))
      (node (ref "R7") (pin "2") (pinfunction "2_2") (pintype "passive"))
      (node (ref "U2") (pin "IN") (pinfunction "IN_IN") (pintype "input"))
    )
    (net (code "80") (name "V135") (class "Default")
      (node (ref "C1") (pin "1") (pinfunction "1_1") (pintype "passive"))
      (node (ref "C16") (pin "1") (pinfunction "1_1") (pintype "passive"))
      (node (ref "C17") (pin "1") (pinfunction "1_1") (pintype "passive"))
      (node (ref "C18") (pin "+") (pinfunction "+_+") (pintype "passive"))
      (node (ref "C2") (pin "1") (pinfunction "1_1") (pintype "passive"))
      (node (ref "C42") (pin "2") (pinfunction "2_2") (pintype "passive"))
      (node (ref "D17") (pin "C") (pinfunction "C_C") (pintype "passive"))
      (node (ref "IC2") (pin "5") (pinfunction "V+_5") (pintype "power_in"))
      (node (ref "Q5") (pin "2") (pinfunction "D_2") (pintype "bidirectional"))
      (node (ref "R32") (pin "2") (pinfunction "2_2") (pintype "passive"))
      (node (ref "R37") (pin "1") (pinfunction "1_1") (pintype "passive"))
      (node (ref "R46") (pin "2") (pinfunction "2_2") (pintype "passive"))
      (node (ref "R8") (pin "1") (pinfunction "1_1") (pintype "passive"))
      (node (ref "U1") (pin "IN") (pinfunction "IN_IN") (pintype "input"))
    )
    (net (code "81") (name "VBAT+") (class "Default")
      (node (ref "C34") (pin "1") (pinfunction "1_1") (pintype "passive"))
      (node (ref "D18") (pin "C") (pinfunction "C_C") (pintype "passive"))
      (node (ref "J1") (pin "1") (pinfunction "1_1") (pintype "passive"))
      (node (ref "Q4") (pin "2") (pinfunction "D_2") (pintype "bidirectional"))
    )
    (net (code "82") (name "VCCIO_FT") (class "Default")
      (node (ref "C26") (pin "1") (pinfunction "1_1") (pintype "passive"))
      (node (ref "U4") (pin "13") (pinfunction "3V3OUT_13") (pintype "bidirectional"))
      (node (ref "U4") (pin "14") (pinfunction "~{RESET}_14") (pintype "bidirectional"))
      (node (ref "U4") (pin "3") (pinfunction "VCCIO_3") (pintype "bidirectional"))
    )
    (net (code "83") (name "VCC_OPAMP") (class "Default")
      (node (ref "C14") (pin "1") (pinfunction "1_1") (pintype "passive"))
      (node (ref "C15") (pin "1") (pinfunction "1_1") (pintype "passive"))
      (node (ref "IC1") (pin "5") (pinfunction "V+_5") (pintype "power_in"))
      (node (ref "R46") (pin "1") (pinfunction "1_1") (pintype "passive"))
    )
    (net (code "84") (name "VIN_LTC2950") (class "Default")
      (node (ref "C20") (pin "1") (pinfunction "1_1") (pintype "passive"))
      (node (ref "C35") (pin "1") (pinfunction "1_1") (pintype "passive"))
      (node (ref "D10") (pin "C") (pinfunction "C_C") (pintype "passive"))
      (node (ref "D9") (pin "C") (pinfunction "C_C") (pintype "passive"))
      (node (ref "Q4") (pin "3") (pinfunction "S_3") (pintype "bidirectional"))
      (node (ref "Q5") (pin "3") (pinfunction "S_3") (pintype "bidirectional"))
      (node (ref "R19") (pin "1") (pinfunction "1_1") (pintype "passive"))
      (node (ref "R50") (pin "2") (pinfunction "2_2") (pintype "passive"))
      (node (ref "R54") (pin "1") (pinfunction "1_1") (pintype "passive"))
      (node (ref "U5") (pin "1") (pinfunction "VIN_1") (pintype "power_in"))
    )
    (net (code "85") (name "VSIG") (class "Default")
      (node (ref "D5") (pin "C") (pinfunction "C_C") (pintype "passive"))
      (node (ref "J5") (pin "1") (pinfunction "1_1") (pintype "passive"))
      (node (ref "R17") (pin "2") (pinfunction "2_2") (pintype "passive"))
    )
    (net (code "86") (name "VUSB_5V") (class "Default")
      (node (ref "C24") (pin "1") (pinfunction "1_1") (pintype "passive"))
      (node (ref "C25") (pin "1") (pinfunction "1_1") (pintype "passive"))
      (node (ref "D11") (pin "A") (pinfunction "A_A") (pintype "passive"))
      (node (ref "L1") (pin "2") (pinfunction "2_2") (pintype "passive"))
      (node (ref "U4") (pin "15") (pinfunction "VCC_15") (pintype "bidirectional"))
    )
    (net (code "87") (name "VUSB_5V_PRE") (class "Default")
      (node (ref "C28") (pin "1") (pinfunction "1_1") (pintype "passive"))
      (node (ref "J3") (pin "VBUS") (pinfunction "VBUS_VBUS") (pintype "power_in"))
      (node (ref "L1") (pin "1") (pinfunction "1_1") (pintype "passive"))
    )
    (net (code "88") (name "unconnected-(J7-Pad1)") (class "Default")
      (node (ref "J7") (pin "1") (pinfunction "1_1") (pintype "passive"))
    )
    (net (code "89") (name "unconnected-(J7-Pad5)") (class "Default")
      (node (ref "J7") (pin "5") (pinfunction "5_5") (pintype "passive"))
    )
    (net (code "90") (name "unconnected-(U3-NC-Pad32)") (class "Default")
      (node (ref "U3") (pin "32") (pinfunction "NC_32") (pintype "bidirectional"))
    )
    (net (code "91") (name "unconnected-(U4-CBUS0-Pad18)") (class "Default")
      (node (ref "U4") (pin "18") (pinfunction "CBUS0_18") (pintype "bidirectional"))
    )
    (net (code "92") (name "unconnected-(U4-CBUS1-Pad17)") (class "Default")
      (node (ref "U4") (pin "17") (pinfunction "CBUS1_17") (pintype "bidirectional"))
    )
    (net (code "93") (name "unconnected-(U4-CBUS2-Pad10)") (class "Default")
      (node (ref "U4") (pin "10") (pinfunction "CBUS2_10") (pintype "bidirectional"))
    )
    (net (code "94") (name "unconnected-(U4-CBUS3-Pad19)") (class "Default")
      (node (ref "U4") (pin "19") (pinfunction "CBUS3_19") (pintype "bidirectional"))
    )
    (net (code "95") (name "unconnected-(U4-~{CTS}-Pad9)") (class "Default")
      (node (ref "U4") (pin "9") (pinfunction "~{CTS}_9") (pintype "bidirectional"))
    )
    (net (code "96") (name "unconnected-(U4-~{DCD}-Pad8)") (class "Default")
      (node (ref "U4") (pin "8") (pinfunction "~{DCD}_8") (pintype "bidirectional"))
    )
    (net (code "97") (name "unconnected-(U4-~{DSR}-Pad7)") (class "Default")
      (node (ref "U4") (pin "7") (pinfunction "~{DSR}_7") (pintype "bidirectional"))
    )
    (net (code "98") (name "unconnected-(U4-~{RI}-Pad5)") (class "Default")
      (node (ref "U4") (pin "5") (pinfunction "~{RI}_5") (pintype "bidirectional"))
    )
    (net (code "99") (name "~{INT}") (class "Default")
      (node (ref "R56") (pin "1") (pinfunction "1_1") (pintype "passive"))
      (node (ref "U5") (pin "5") (pinfunction "~{INT}_5") (pintype "output"))
    )
    (net (code "100") (name "~{KILL}") (class "Default")
      (node (ref "D19") (pin "C") (pinfunction "C_C") (pintype "passive"))
      (node (ref "R37") (pin "2") (pinfunction "2_2") (pintype "passive"))
      (node (ref "R52") (pin "1") (pinfunction "1_1") (pintype "passive"))
      (node (ref "R55") (pin "1") (pinfunction "1_1") (pintype "passive"))
      (node (ref "U5") (pin "8") (pinfunction "~{KILL}_8") (pintype "input"))
    )
    (net (code "101") (name "~{PB1}") (class "Default")
      (node (ref "C22") (pin "1") (pinfunction "1_1") (pintype "passive"))
      (node (ref "R18") (pin "2") (pinfunction "2_2") (pintype "passive"))
      (node (ref "R19") (pin "2") (pinfunction "2_2") (pintype "passive"))
      (node (ref "S2") (pin "2") (pinfunction "2_2") (pintype "passive"))
    )
    (net (code "102") (name "~{PB}") (class "Default")
      (node (ref "R18") (pin "1") (pinfunction "1_1") (pintype "passive"))
      (node (ref "U5") (pin "2") (pinfunction "~{PB}_2") (pintype "input"))
    )
  )
)
